# quark_dog_control.net
KiCad netlist of a schematic drawn in Altium Designer
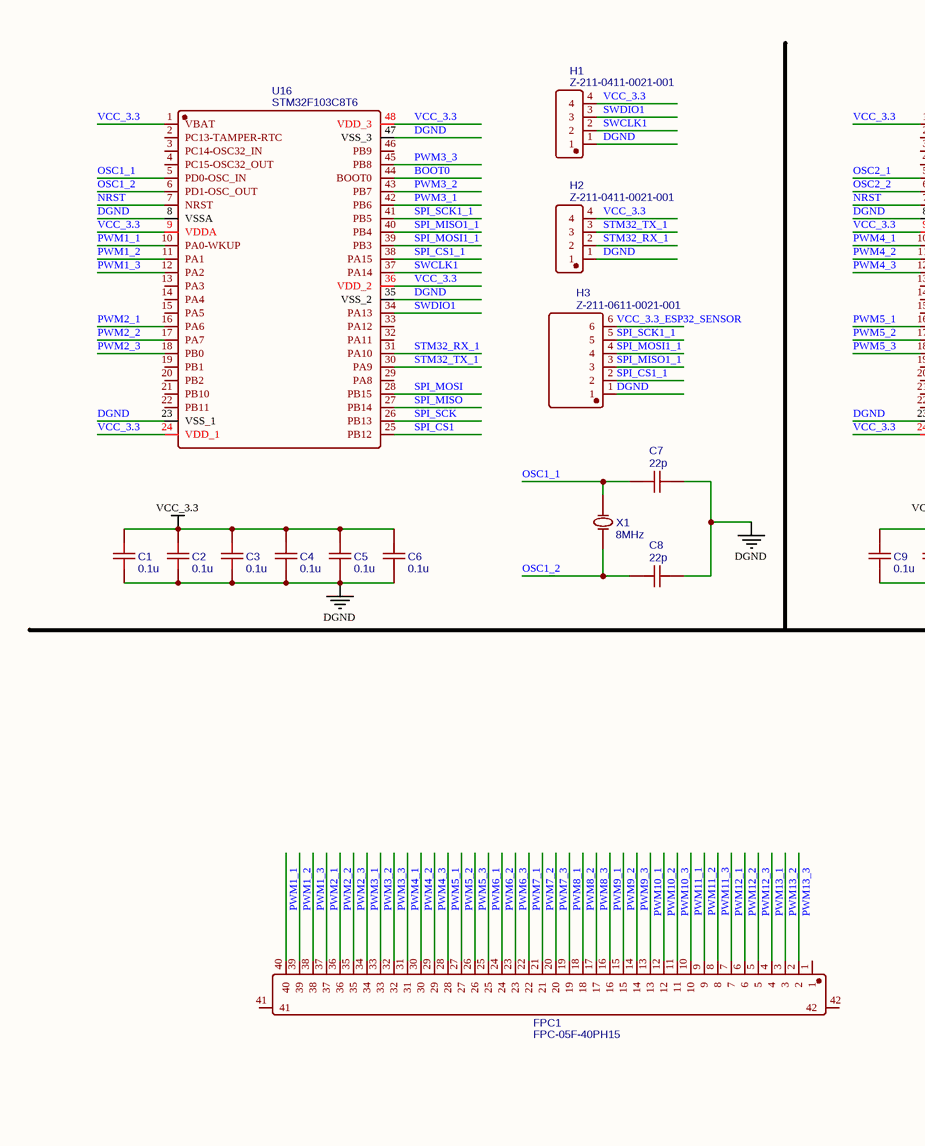
[diagram p0: quark_dog_control.schdoc, left]
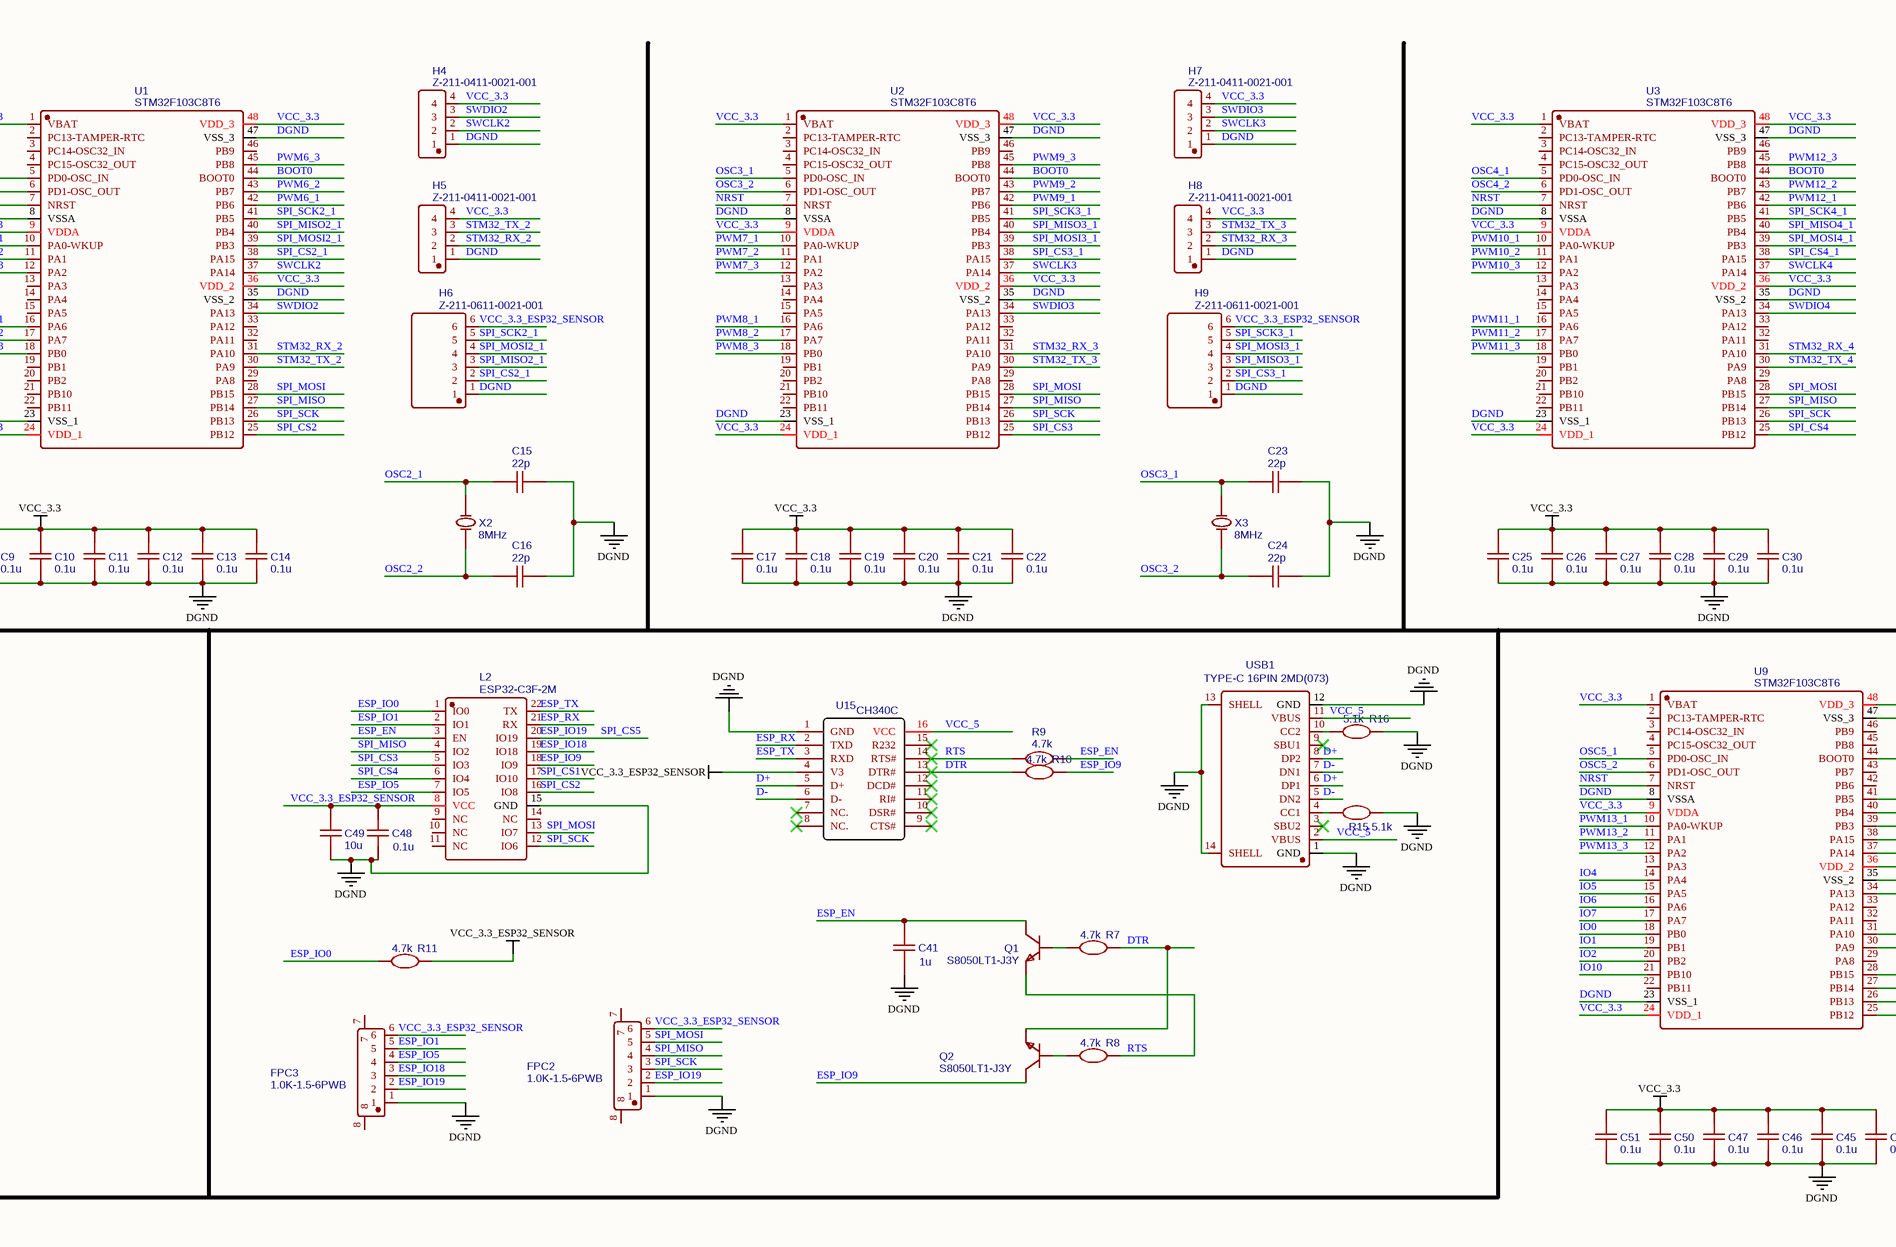
[diagram p1: quark_dog_control.schdoc, middle]
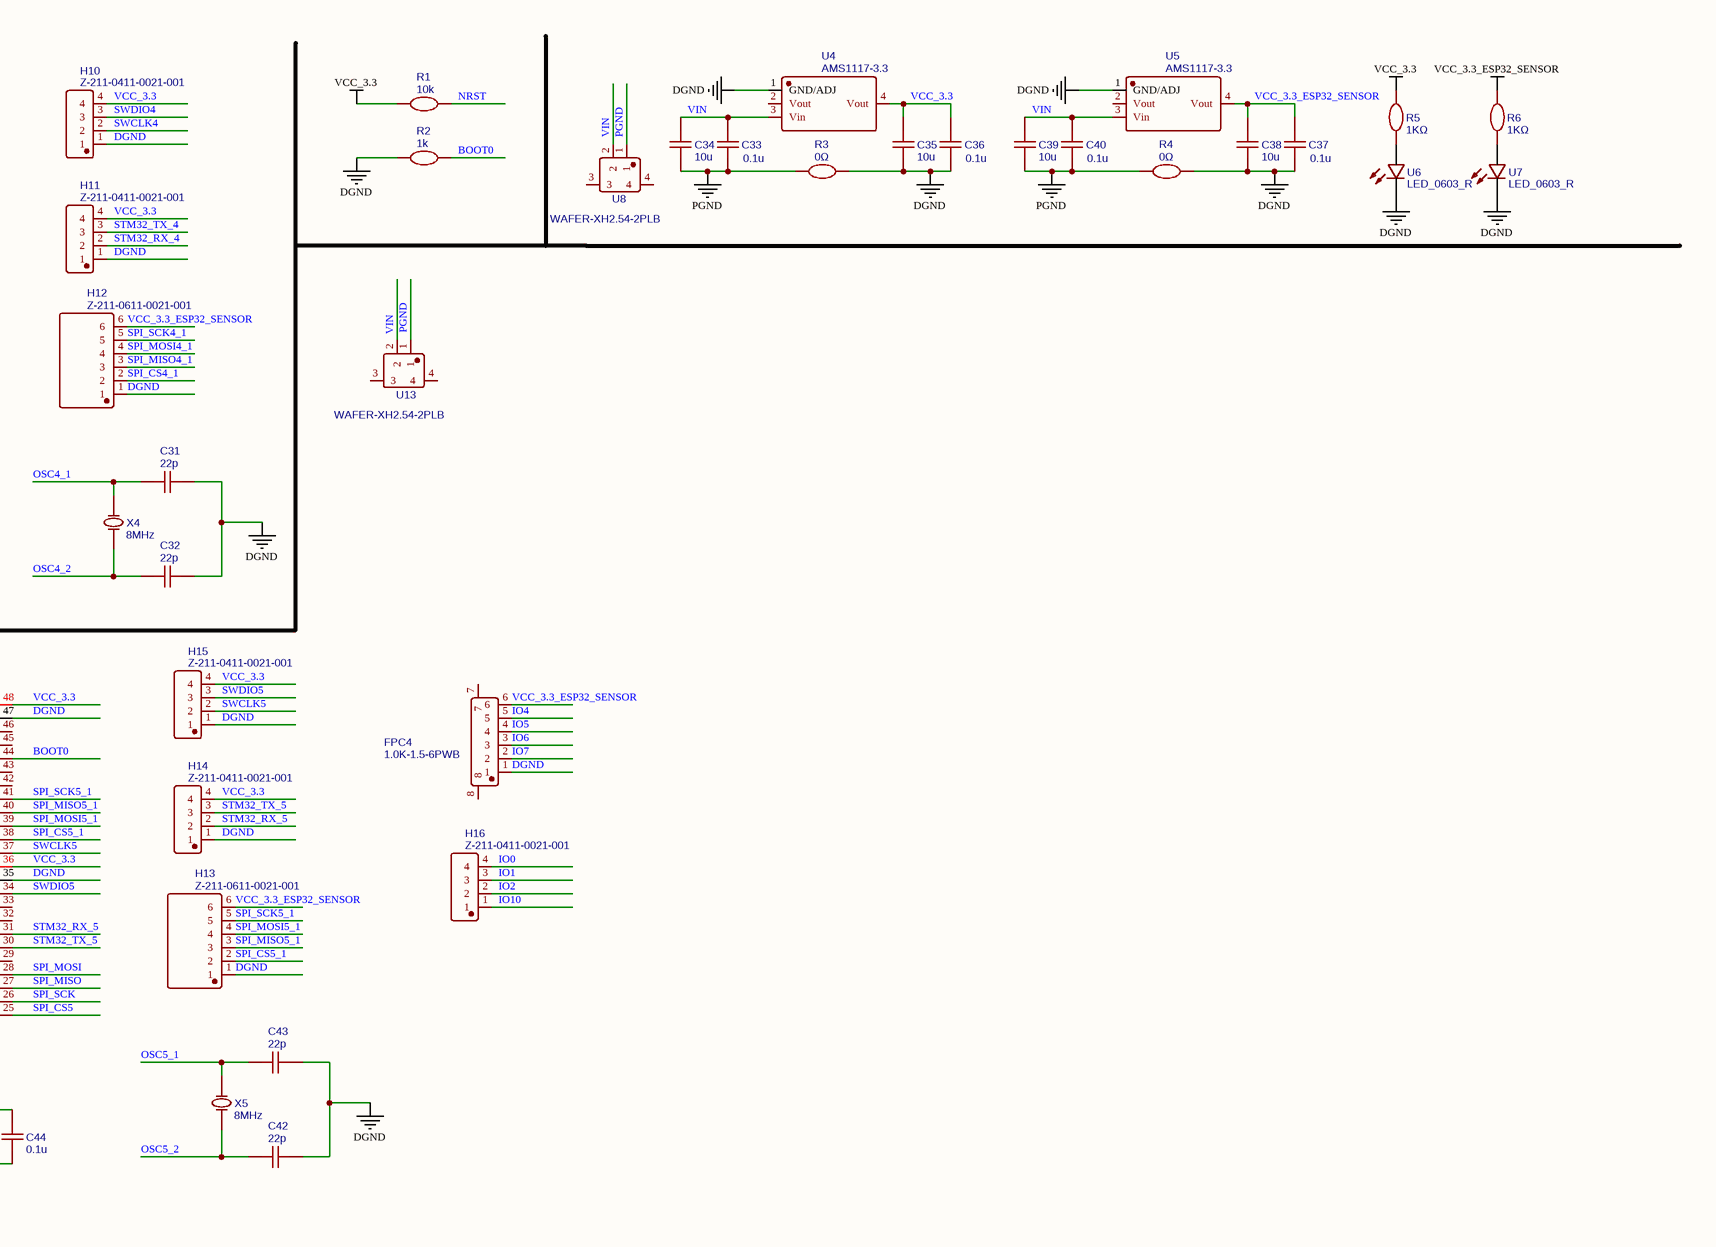
[diagram p2: quark_dog_control.schdoc, right]

(export (version "E")
  (design (tool "Eeschema 10.0.6"))
  (components
    (comp (ref "C1")
      (value "0.1u")
      (footprint "C0603")
      (fields (field (name "CONTRIBUTOR") "LCEDA_Lib"))
      (libsource (lib "altium-import") (part "root_1_0.1u_"))
    )
    (comp (ref "C2")
      (value "0.1u")
      (footprint "C0603")
      (fields (field (name "CONTRIBUTOR") "LCEDA_Lib"))
      (libsource (lib "altium-import") (part "root_1_0.1u_"))
    )
    (comp (ref "C3")
      (value "0.1u")
      (footprint "C0603")
      (fields (field (name "CONTRIBUTOR") "LCEDA_Lib"))
      (libsource (lib "altium-import") (part "root_1_0.1u_"))
    )
    (comp (ref "C4")
      (value "0.1u")
      (footprint "C0603")
      (fields (field (name "CONTRIBUTOR") "LCEDA_Lib"))
      (libsource (lib "altium-import") (part "root_1_0.1u_"))
    )
    (comp (ref "C5")
      (value "0.1u")
      (footprint "C0603")
      (fields (field (name "CONTRIBUTOR") "LCEDA_Lib"))
      (libsource (lib "altium-import") (part "root_1_0.1u_"))
    )
    (comp (ref "C6")
      (value "0.1u")
      (footprint "C0603")
      (fields (field (name "CONTRIBUTOR") "LCEDA_Lib"))
      (libsource (lib "altium-import") (part "root_1_0.1u_"))
    )
    (comp (ref "C7")
      (value "22p")
      (footprint "C0603")
      (fields (field (name "CONTRIBUTOR") "LCEDA_Lib"))
      (libsource (lib "altium-import") (part "root_2_22p_"))
    )
    (comp (ref "C8")
      (value "22p")
      (footprint "C0603")
      (fields (field (name "CONTRIBUTOR") "LCEDA_Lib"))
      (libsource (lib "altium-import") (part "root_0_22p_"))
    )
    (comp (ref "C9")
      (value "0.1u")
      (footprint "C0603")
      (fields (field (name "CONTRIBUTOR") "LCEDA_Lib"))
      (libsource (lib "altium-import") (part "root_1_0.1u_"))
    )
    (comp (ref "C10")
      (value "0.1u")
      (footprint "C0603")
      (fields (field (name "CONTRIBUTOR") "LCEDA_Lib"))
      (libsource (lib "altium-import") (part "root_1_0.1u_"))
    )
    (comp (ref "C11")
      (value "0.1u")
      (footprint "C0603")
      (fields (field (name "CONTRIBUTOR") "LCEDA_Lib"))
      (libsource (lib "altium-import") (part "root_1_0.1u_"))
    )
    (comp (ref "C12")
      (value "0.1u")
      (footprint "C0603")
      (fields (field (name "CONTRIBUTOR") "LCEDA_Lib"))
      (libsource (lib "altium-import") (part "root_1_0.1u_"))
    )
    (comp (ref "C13")
      (value "0.1u")
      (footprint "C0603")
      (fields (field (name "CONTRIBUTOR") "LCEDA_Lib"))
      (libsource (lib "altium-import") (part "root_1_0.1u_"))
    )
    (comp (ref "C14")
      (value "0.1u")
      (footprint "C0603")
      (fields (field (name "CONTRIBUTOR") "LCEDA_Lib"))
      (libsource (lib "altium-import") (part "root_1_0.1u_"))
    )
    (comp (ref "C15")
      (value "22p")
      (footprint "C0603")
      (fields (field (name "CONTRIBUTOR") "LCEDA_Lib"))
      (libsource (lib "altium-import") (part "root_2_22p_"))
    )
    (comp (ref "C16")
      (value "22p")
      (footprint "C0603")
      (fields (field (name "CONTRIBUTOR") "LCEDA_Lib"))
      (libsource (lib "altium-import") (part "root_0_22p_"))
    )
    (comp (ref "C17")
      (value "0.1u")
      (footprint "C0603")
      (fields (field (name "CONTRIBUTOR") "LCEDA_Lib"))
      (libsource (lib "altium-import") (part "root_1_0.1u_"))
    )
    (comp (ref "C18")
      (value "0.1u")
      (footprint "C0603")
      (fields (field (name "CONTRIBUTOR") "LCEDA_Lib"))
      (libsource (lib "altium-import") (part "root_1_0.1u_"))
    )
    (comp (ref "C19")
      (value "0.1u")
      (footprint "C0603")
      (fields (field (name "CONTRIBUTOR") "LCEDA_Lib"))
      (libsource (lib "altium-import") (part "root_1_0.1u_"))
    )
    (comp (ref "C20")
      (value "0.1u")
      (footprint "C0603")
      (fields (field (name "CONTRIBUTOR") "LCEDA_Lib"))
      (libsource (lib "altium-import") (part "root_1_0.1u_"))
    )
    (comp (ref "C21")
      (value "0.1u")
      (footprint "C0603")
      (fields (field (name "CONTRIBUTOR") "LCEDA_Lib"))
      (libsource (lib "altium-import") (part "root_1_0.1u_"))
    )
    (comp (ref "C22")
      (value "0.1u")
      (footprint "C0603")
      (fields (field (name "CONTRIBUTOR") "LCEDA_Lib"))
      (libsource (lib "altium-import") (part "root_1_0.1u_"))
    )
    (comp (ref "C23")
      (value "22p")
      (footprint "C0603")
      (fields (field (name "CONTRIBUTOR") "LCEDA_Lib"))
      (libsource (lib "altium-import") (part "root_2_22p_"))
    )
    (comp (ref "C24")
      (value "22p")
      (footprint "C0603")
      (fields (field (name "CONTRIBUTOR") "LCEDA_Lib"))
      (libsource (lib "altium-import") (part "root_0_22p_"))
    )
    (comp (ref "C25")
      (value "0.1u")
      (footprint "C0603")
      (fields (field (name "CONTRIBUTOR") "LCEDA_Lib"))
      (libsource (lib "altium-import") (part "root_1_0.1u_"))
    )
    (comp (ref "C26")
      (value "0.1u")
      (footprint "C0603")
      (fields (field (name "CONTRIBUTOR") "LCEDA_Lib"))
      (libsource (lib "altium-import") (part "root_1_0.1u_"))
    )
    (comp (ref "C27")
      (value "0.1u")
      (footprint "C0603")
      (fields (field (name "CONTRIBUTOR") "LCEDA_Lib"))
      (libsource (lib "altium-import") (part "root_1_0.1u_"))
    )
    (comp (ref "C28")
      (value "0.1u")
      (footprint "C0603")
      (fields (field (name "CONTRIBUTOR") "LCEDA_Lib"))
      (libsource (lib "altium-import") (part "root_1_0.1u_"))
    )
    (comp (ref "C29")
      (value "0.1u")
      (footprint "C0603")
      (fields (field (name "CONTRIBUTOR") "LCEDA_Lib"))
      (libsource (lib "altium-import") (part "root_1_0.1u_"))
    )
    (comp (ref "C30")
      (value "0.1u")
      (footprint "C0603")
      (fields (field (name "CONTRIBUTOR") "LCEDA_Lib"))
      (libsource (lib "altium-import") (part "root_1_0.1u_"))
    )
    (comp (ref "C31")
      (value "22p")
      (footprint "C0603")
      (fields (field (name "CONTRIBUTOR") "LCEDA_Lib"))
      (libsource (lib "altium-import") (part "root_2_22p_"))
    )
    (comp (ref "C32")
      (value "22p")
      (footprint "C0603")
      (fields (field (name "CONTRIBUTOR") "LCEDA_Lib"))
      (libsource (lib "altium-import") (part "root_0_22p_"))
    )
    (comp (ref "C33")
      (value "0.1u")
      (footprint "C0603")
      (fields (field (name "CONTRIBUTOR") "LCEDA_Lib"))
      (libsource (lib "altium-import") (part "root_1_0.1u_"))
    )
    (comp (ref "C34")
      (value "10u")
      (footprint "C0603")
      (fields (field (name "CONTRIBUTOR") "LCEDA_Lib"))
      (libsource (lib "altium-import") (part "root_1_10u_"))
    )
    (comp (ref "C35")
      (value "10u")
      (footprint "C0603")
      (fields (field (name "CONTRIBUTOR") "LCEDA_Lib"))
      (libsource (lib "altium-import") (part "root_1_10u_"))
    )
    (comp (ref "C36")
      (value "0.1u")
      (footprint "C0603")
      (fields (field (name "CONTRIBUTOR") "LCEDA_Lib"))
      (libsource (lib "altium-import") (part "root_1_0.1u_"))
    )
    (comp (ref "C37")
      (value "0.1u")
      (footprint "C0603")
      (fields (field (name "CONTRIBUTOR") "LCEDA_Lib"))
      (libsource (lib "altium-import") (part "root_1_0.1u_"))
    )
    (comp (ref "C38")
      (value "10u")
      (footprint "C0603")
      (fields (field (name "CONTRIBUTOR") "LCEDA_Lib"))
      (libsource (lib "altium-import") (part "root_1_10u_"))
    )
    (comp (ref "C39")
      (value "10u")
      (footprint "C0603")
      (fields (field (name "CONTRIBUTOR") "LCEDA_Lib"))
      (libsource (lib "altium-import") (part "root_1_10u_"))
    )
    (comp (ref "C40")
      (value "0.1u")
      (footprint "C0603")
      (fields (field (name "CONTRIBUTOR") "LCEDA_Lib"))
      (libsource (lib "altium-import") (part "root_1_0.1u_"))
    )
    (comp (ref "C41")
      (value "1u")
      (footprint "C0603")
      (fields (field (name "CONTRIBUTOR") "LCEDA_Lib"))
      (libsource (lib "altium-import") (part "root_1_1u_"))
    )
    (comp (ref "C42")
      (value "22p")
      (footprint "C0603")
      (fields (field (name "CONTRIBUTOR") "LCEDA_Lib"))
      (libsource (lib "altium-import") (part "root_0_22p_"))
    )
    (comp (ref "C43")
      (value "22p")
      (footprint "C0603")
      (fields (field (name "CONTRIBUTOR") "LCEDA_Lib"))
      (libsource (lib "altium-import") (part "root_2_22p_"))
    )
    (comp (ref "C44")
      (value "0.1u")
      (footprint "C0603")
      (fields (field (name "CONTRIBUTOR") "LCEDA_Lib"))
      (libsource (lib "altium-import") (part "root_1_0.1u_"))
    )
    (comp (ref "C45")
      (value "0.1u")
      (footprint "C0603")
      (fields (field (name "CONTRIBUTOR") "LCEDA_Lib"))
      (libsource (lib "altium-import") (part "root_1_0.1u_"))
    )
    (comp (ref "C46")
      (value "0.1u")
      (footprint "C0603")
      (fields (field (name "CONTRIBUTOR") "LCEDA_Lib"))
      (libsource (lib "altium-import") (part "root_1_0.1u_"))
    )
    (comp (ref "C47")
      (value "0.1u")
      (footprint "C0603")
      (fields (field (name "CONTRIBUTOR") "LCEDA_Lib"))
      (libsource (lib "altium-import") (part "root_1_0.1u_"))
    )
    (comp (ref "C48")
      (value "0.1u")
      (footprint "C0603")
      (fields (field (name "CONTRIBUTOR") "LCEDA_Lib"))
      (libsource (lib "altium-import") (part "root_1_0.1u_"))
    )
    (comp (ref "C49")
      (value "10u")
      (footprint "C0603")
      (fields (field (name "CONTRIBUTOR") "LCEDA_Lib"))
      (libsource (lib "altium-import") (part "root_1_10u_"))
    )
    (comp (ref "C50")
      (value "0.1u")
      (footprint "C0603")
      (fields (field (name "CONTRIBUTOR") "LCEDA_Lib"))
      (libsource (lib "altium-import") (part "root_1_0.1u_"))
    )
    (comp (ref "C51")
      (value "0.1u")
      (footprint "C0603")
      (fields (field (name "CONTRIBUTOR") "LCEDA_Lib"))
      (libsource (lib "altium-import") (part "root_1_0.1u_"))
    )
    (comp (ref "FPC1")
      (value "FPC-05F-40PH15")
      (footprint "FPC-SMD_40P-P0.50_FPC-05F-40PH15")
      (fields (field (name "BOM_SUPPLIER PART") "C2856825") (field (name "CONTRIBUTOR") "LCSC"))
      (libsource (lib "altium-import") (part "root_3_FPC-05F-40PH15_"))
    )
    (comp (ref "FPC2")
      (value "1.0K-1.5-6PWB")
      (footprint "FPC-SMD_6P-P1.00_HDGC_1.0K-1.5-6PWB")
      (fields (field (name "BOM_SUPPLIER PART") "C2919568") (field (name "CONTRIBUTOR") "LCSC"))
      (libsource (lib "altium-import") (part "root_2_1.0K-1.5-6PWB_"))
    )
    (comp (ref "FPC3")
      (value "1.0K-1.5-6PWB")
      (footprint "FPC-SMD_6P-P1.00_HDGC_1.0K-1.5-6PWB")
      (fields (field (name "BOM_SUPPLIER PART") "C2919568") (field (name "CONTRIBUTOR") "LCSC"))
      (libsource (lib "altium-import") (part "root_2_1.0K-1.5-6PWB_"))
    )
    (comp (ref "FPC4")
      (value "1.0K-1.5-6PWB")
      (footprint "FPC-SMD_6P-P1.00_HDGC_1.0K-1.5-6PWB")
      (fields (field (name "BOM_SUPPLIER PART") "C2919568") (field (name "CONTRIBUTOR") "LCSC"))
      (libsource (lib "altium-import") (part "root_2_1.0K-1.5-6PWB_"))
    )
    (comp (ref "H1")
      (value "Z-211-0411-0021-001")
      (footprint "HDR-TH_4P-P2.54-V-M")
      (fields (field (name "BOM_SUPPLIER PART") "C152150") (field (name "CONTRIBUTOR") "LCSC"))
      (libsource (lib "altium-import") (part "root_2_Z-211-0411-0021-001_"))
    )
    (comp (ref "H2")
      (value "Z-211-0411-0021-001")
      (footprint "HDR-TH_4P-P2.54-V-M")
      (fields (field (name "BOM_SUPPLIER PART") "C152150") (field (name "CONTRIBUTOR") "LCSC"))
      (libsource (lib "altium-import") (part "root_2_Z-211-0411-0021-001_"))
    )
    (comp (ref "H3")
      (value "Z-211-0611-0021-001")
      (footprint "HDR-TH_6P-P2.54-V_Z-211-0611-0021-001")
      (fields (field (name "BOM_SUPPLIER PART") "C190819") (field (name "CONTRIBUTOR") "LCSC"))
      (libsource (lib "altium-import") (part "root_2_Z-211-0611-0021-001_"))
    )
    (comp (ref "H4")
      (value "Z-211-0411-0021-001")
      (footprint "HDR-TH_4P-P2.54-V-M")
      (fields (field (name "BOM_SUPPLIER PART") "C152150") (field (name "CONTRIBUTOR") "LCSC"))
      (libsource (lib "altium-import") (part "root_2_Z-211-0411-0021-001_"))
    )
    (comp (ref "H5")
      (value "Z-211-0411-0021-001")
      (footprint "HDR-TH_4P-P2.54-V-M")
      (fields (field (name "BOM_SUPPLIER PART") "C152150") (field (name "CONTRIBUTOR") "LCSC"))
      (libsource (lib "altium-import") (part "root_2_Z-211-0411-0021-001_"))
    )
    (comp (ref "H6")
      (value "Z-211-0611-0021-001")
      (footprint "HDR-TH_6P-P2.54-V_Z-211-0611-0021-001")
      (fields (field (name "BOM_SUPPLIER PART") "C190819") (field (name "CONTRIBUTOR") "LCSC"))
      (libsource (lib "altium-import") (part "root_2_Z-211-0611-0021-001_"))
    )
    (comp (ref "H7")
      (value "Z-211-0411-0021-001")
      (footprint "HDR-TH_4P-P2.54-V-M")
      (fields (field (name "BOM_SUPPLIER PART") "C152150") (field (name "CONTRIBUTOR") "LCSC"))
      (libsource (lib "altium-import") (part "root_2_Z-211-0411-0021-001_"))
    )
    (comp (ref "H8")
      (value "Z-211-0411-0021-001")
      (footprint "HDR-TH_4P-P2.54-V-M")
      (fields (field (name "BOM_SUPPLIER PART") "C152150") (field (name "CONTRIBUTOR") "LCSC"))
      (libsource (lib "altium-import") (part "root_2_Z-211-0411-0021-001_"))
    )
    (comp (ref "H9")
      (value "Z-211-0611-0021-001")
      (footprint "HDR-TH_6P-P2.54-V_Z-211-0611-0021-001")
      (fields (field (name "BOM_SUPPLIER PART") "C190819") (field (name "CONTRIBUTOR") "LCSC"))
      (libsource (lib "altium-import") (part "root_2_Z-211-0611-0021-001_"))
    )
    (comp (ref "H10")
      (value "Z-211-0411-0021-001")
      (footprint "HDR-TH_4P-P2.54-V-M")
      (fields (field (name "BOM_SUPPLIER PART") "C152150") (field (name "CONTRIBUTOR") "LCSC"))
      (libsource (lib "altium-import") (part "root_2_Z-211-0411-0021-001_"))
    )
    (comp (ref "H11")
      (value "Z-211-0411-0021-001")
      (footprint "HDR-TH_4P-P2.54-V-M")
      (fields (field (name "BOM_SUPPLIER PART") "C152150") (field (name "CONTRIBUTOR") "LCSC"))
      (libsource (lib "altium-import") (part "root_2_Z-211-0411-0021-001_"))
    )
    (comp (ref "H12")
      (value "Z-211-0611-0021-001")
      (footprint "HDR-TH_6P-P2.54-V_Z-211-0611-0021-001")
      (fields (field (name "BOM_SUPPLIER PART") "C190819") (field (name "CONTRIBUTOR") "LCSC"))
      (libsource (lib "altium-import") (part "root_2_Z-211-0611-0021-001_"))
    )
    (comp (ref "H13")
      (value "Z-211-0611-0021-001")
      (footprint "HDR-TH_6P-P2.54-V_Z-211-0611-0021-001")
      (fields (field (name "BOM_SUPPLIER PART") "C190819") (field (name "CONTRIBUTOR") "LCSC"))
      (libsource (lib "altium-import") (part "root_2_Z-211-0611-0021-001_"))
    )
    (comp (ref "H14")
      (value "Z-211-0411-0021-001")
      (footprint "HDR-TH_4P-P2.54-V-M")
      (fields (field (name "BOM_SUPPLIER PART") "C152150") (field (name "CONTRIBUTOR") "LCSC"))
      (libsource (lib "altium-import") (part "root_2_Z-211-0411-0021-001_"))
    )
    (comp (ref "H15")
      (value "Z-211-0411-0021-001")
      (footprint "HDR-TH_4P-P2.54-V-M")
      (fields (field (name "BOM_SUPPLIER PART") "C152150") (field (name "CONTRIBUTOR") "LCSC"))
      (libsource (lib "altium-import") (part "root_2_Z-211-0411-0021-001_"))
    )
    (comp (ref "H16")
      (value "Z-211-0411-0021-001")
      (footprint "HDR-TH_4P-P2.54-V-M")
      (fields (field (name "BOM_SUPPLIER PART") "C152150") (field (name "CONTRIBUTOR") "LCSC"))
      (libsource (lib "altium-import") (part "root_2_Z-211-0411-0021-001_"))
    )
    (comp (ref "L2")
      (value "ESP32-C3F-2M")
      (footprint "WIFIM-SMD_ESP32-C3F-2M")
      (fields (field (name "BOM_SUPPLIER PART") "C2830867") (field (name "CONTRIBUTOR") "LCSC"))
      (libsource (lib "altium-import") (part "root_0_ESP32-C3F-2M_"))
    )
    (comp (ref "Q1")
      (value "S8050LT1-J3Y")
      (footprint "SOT-23_L2.9-W1.3-P1.90-LS2.4-BR")
      (fields (field (name "BOM_SUPPLIER PART") "C2962087") (field (name "CONTRIBUTOR") "lcsc"))
      (libsource (lib "altium-import") (part "root_0_S8050LT1-J3Y_"))
    )
    (comp (ref "Q2")
      (value "S8050LT1-J3Y")
      (footprint "SOT-23_L2.9-W1.3-P1.90-LS2.4-BR")
      (fields (field (name "BOM_SUPPLIER PART") "C2962087") (field (name "CONTRIBUTOR") "lcsc"))
      (libsource (lib "altium-import") (part "root_2_S8050LT1-J3Y_"))
    )
    (comp (ref "R1")
      (value "10k")
      (footprint "R0603")
      (fields (field (name "CONTRIBUTOR") "LCEDA_Lib"))
      (libsource (lib "altium-import") (part "root_0_10k_"))
    )
    (comp (ref "R2")
      (value "1k")
      (footprint "R0603")
      (fields (field (name "CONTRIBUTOR") "LCEDA_Lib"))
      (libsource (lib "altium-import") (part "root_0_1k_"))
    )
    (comp (ref "R3")
      (value "0Ω")
      (footprint "R0603")
      (fields (field (name "CONTRIBUTOR") "LCEDA_Lib"))
      (libsource (lib "altium-import") (part "root_0_0Ω_"))
    )
    (comp (ref "R4")
      (value "0Ω")
      (footprint "R0603")
      (fields (field (name "CONTRIBUTOR") "LCEDA_Lib"))
      (libsource (lib "altium-import") (part "root_0_0Ω_"))
    )
    (comp (ref "R5")
      (value "1KΩ")
      (footprint "R0603")
      (fields (field (name "CONTRIBUTOR") "LCEDA_Lib"))
      (libsource (lib "altium-import") (part "root_1_1KΩ_"))
    )
    (comp (ref "R6")
      (value "1KΩ")
      (footprint "R0603")
      (fields (field (name "CONTRIBUTOR") "LCEDA_Lib"))
      (libsource (lib "altium-import") (part "root_3_1KΩ_"))
    )
    (comp (ref "R7")
      (value "4.7k")
      (footprint "R0603")
      (fields (field (name "CONTRIBUTOR") "LCEDA_Lib"))
      (libsource (lib "altium-import") (part "root_0_4.7k_"))
    )
    (comp (ref "R8")
      (value "4.7k")
      (footprint "R0603")
      (fields (field (name "CONTRIBUTOR") "LCEDA_Lib"))
      (libsource (lib "altium-import") (part "root_0_4.7k_"))
    )
    (comp (ref "R9")
      (value "4.7k")
      (footprint "R0603")
      (fields (field (name "CONTRIBUTOR") "LCEDA_Lib"))
      (libsource (lib "altium-import") (part "root_2_4.7k_"))
    )
    (comp (ref "R10")
      (value "4.7k")
      (footprint "R0603")
      (fields (field (name "CONTRIBUTOR") "LCEDA_Lib"))
      (libsource (lib "altium-import") (part "root_0_4.7k_"))
    )
    (comp (ref "R11")
      (value "4.7k")
      (footprint "R0603")
      (fields (field (name "CONTRIBUTOR") "LCEDA_Lib"))
      (libsource (lib "altium-import") (part "root_0_4.7k_"))
    )
    (comp (ref "R15")
      (value "5.1k")
      (footprint "R0603")
      (fields (field (name "CONTRIBUTOR") "LCEDA_Lib"))
      (libsource (lib "altium-import") (part "root_0_5.1k_"))
    )
    (comp (ref "R16")
      (value "5.1k")
      (footprint "R0603")
      (fields (field (name "CONTRIBUTOR") "LCEDA_Lib"))
      (libsource (lib "altium-import") (part "root_0_5.1k_"))
    )
    (comp (ref "U1")
      (value "STM32F103C8T6")
      (footprint "LQFP-48_L7.0-W7.0-P0.50-LS9.0-BL")
      (fields (field (name "BOM_SUPPLIER PART") "C8734"))
      (libsource (lib "altium-import") (part "root_0_STM32F103C8T6_"))
    )
    (comp (ref "U2")
      (value "STM32F103C8T6")
      (footprint "LQFP-48_L7.0-W7.0-P0.50-LS9.0-BL")
      (fields (field (name "BOM_SUPPLIER PART") "C8734"))
      (libsource (lib "altium-import") (part "root_0_STM32F103C8T6_"))
    )
    (comp (ref "U3")
      (value "STM32F103C8T6")
      (footprint "LQFP-48_L7.0-W7.0-P0.50-LS9.0-BL")
      (fields (field (name "BOM_SUPPLIER PART") "C8734"))
      (libsource (lib "altium-import") (part "root_0_STM32F103C8T6_"))
    )
    (comp (ref "U4")
      (value "AMS1117-3.3")
      (footprint "SOT-223-3_L6.5-W3.4-P2.30-LS7.0-BR")
      (fields (field (name "BOM_SUPPLIER PART") "C6186"))
      (libsource (lib "altium-import") (part "root_0_AMS1117-3.3_"))
    )
    (comp (ref "U5")
      (value "AMS1117-3.3")
      (footprint "SOT-223-3_L6.5-W3.4-P2.30-LS7.0-BR")
      (fields (field (name "BOM_SUPPLIER PART") "C6186"))
      (libsource (lib "altium-import") (part "root_0_AMS1117-3.3_"))
    )
    (comp (ref "U6")
      (value "LED_0603_R")
      (footprint "LED0603-RD")
      (fields (field (name "BOM_SUPPLIER PART") "C9900016084") (field (name "CONTRIBUTOR") "lcsc"))
      (libsource (lib "altium-import") (part "root_1_LED_0603_R_"))
    )
    (comp (ref "U7")
      (value "LED_0603_R")
      (footprint "LED0603-RD")
      (fields (field (name "BOM_SUPPLIER PART") "C9900016084") (field (name "CONTRIBUTOR") "lcsc"))
      (libsource (lib "altium-import") (part "root_1_LED_0603_R_"))
    )
    (comp (ref "U8")
      (value "WAFER-XH2.54-2PLB")
      (footprint "CONN-SMD_2P-P2.50_XUNPU_WAFER-XH2.54-2PLB")
      (fields (field (name "BOM_SUPPLIER PART") "C3029467") (field (name "CONTRIBUTOR") "lcsc"))
      (libsource (lib "altium-import") (part "root_3_WAFER-XH2.54-2PLB_"))
    )
    (comp (ref "U9")
      (value "STM32F103C8T6")
      (footprint "LQFP-48_L7.0-W7.0-P0.50-LS9.0-BL")
      (fields (field (name "BOM_SUPPLIER PART") "C8734"))
      (libsource (lib "altium-import") (part "root_0_STM32F103C8T6_"))
    )
    (comp (ref "U13")
      (value "WAFER-XH2.54-2PLB")
      (footprint "CONN-SMD_2P-P2.50_XUNPU_WAFER-XH2.54-2PLB")
      (fields (field (name "BOM_SUPPLIER PART") "C3029467") (field (name "CONTRIBUTOR") "lcsc"))
      (libsource (lib "altium-import") (part "root_3_WAFER-XH2.54-2PLB_"))
    )
    (comp (ref "U15")
      (value "CH340C")
      (footprint "SOP-16_L10.0-W3.9-P1.27-LS6.0-BL")
      (fields (field (name "BOM_SUPPLIER PART") "C84681"))
      (libsource (lib "altium-import") (part "root_0_CH340C_"))
    )
    (comp (ref "U16")
      (value "STM32F103C8T6")
      (footprint "LQFP-48_L7.0-W7.0-P0.50-LS9.0-BL")
      (fields (field (name "BOM_SUPPLIER PART") "C8734"))
      (libsource (lib "altium-import") (part "root_0_STM32F103C8T6_"))
    )
    (comp (ref "USB1")
      (value "TYPE-C 16PIN 2MD(073)")
      (footprint "USB-C-SMD_TYPE-C-6PIN-2MD-073")
      (fields (field (name "BOM_SUPPLIER PART") "C2765186") (field (name "CONTRIBUTOR") "LCSC"))
      (libsource (lib "altium-import") (part "root_2_TYPE-C 16PIN 2MD(073)_"))
    )
    (comp (ref "X1")
      (value "8MHz")
      (footprint "OSC-SMD_L5.0-W3.2")
      (fields
        (field (name "BOM_SUPPLIER PART") "C331616")
        (field (name "BOM_MANUFACTURER PART") "7A08000001")
        (field (name "CONTRIBUTOR") "LCSC")
      )
      (libsource (lib "altium-import") (part "root_1_8MHz_"))
    )
    (comp (ref "X2")
      (value "8MHz")
      (footprint "OSC-SMD_L5.0-W3.2")
      (fields
        (field (name "BOM_SUPPLIER PART") "C331616")
        (field (name "BOM_MANUFACTURER PART") "7A08000001")
        (field (name "CONTRIBUTOR") "LCSC")
      )
      (libsource (lib "altium-import") (part "root_1_8MHz_"))
    )
    (comp (ref "X3")
      (value "8MHz")
      (footprint "OSC-SMD_L5.0-W3.2")
      (fields
        (field (name "BOM_SUPPLIER PART") "C331616")
        (field (name "BOM_MANUFACTURER PART") "7A08000001")
        (field (name "CONTRIBUTOR") "LCSC")
      )
      (libsource (lib "altium-import") (part "root_1_8MHz_"))
    )
    (comp (ref "X4")
      (value "8MHz")
      (footprint "OSC-SMD_L5.0-W3.2")
      (fields
        (field (name "BOM_SUPPLIER PART") "C331616")
        (field (name "BOM_MANUFACTURER PART") "7A08000001")
        (field (name "CONTRIBUTOR") "LCSC")
      )
      (libsource (lib "altium-import") (part "root_1_8MHz_"))
    )
    (comp (ref "X5")
      (value "8MHz")
      (footprint "OSC-SMD_L5.0-W3.2")
      (fields
        (field (name "BOM_SUPPLIER PART") "C331616")
        (field (name "BOM_MANUFACTURER PART") "7A08000001")
        (field (name "CONTRIBUTOR") "LCSC")
      )
      (libsource (lib "altium-import") (part "root_1_8MHz_"))
    )
  )
  (nets
    (net (code "1") (name "/BOOT0") (class "Default")
      (node (ref "R2") (pin "2") (pinfunction "2_2") (pintype "passive"))
      (node (ref "U1") (pin "44") (pinfunction "BOOT0_44") (pintype "passive"))
      (node (ref "U16") (pin "44") (pinfunction "BOOT0_44") (pintype "passive"))
      (node (ref "U2") (pin "44") (pinfunction "BOOT0_44") (pintype "passive"))
      (node (ref "U3") (pin "44") (pinfunction "BOOT0_44") (pintype "passive"))
      (node (ref "U9") (pin "44") (pinfunction "BOOT0_44") (pintype "passive"))
    )
    (net (code "2") (name "/D+") (class "Default")
      (node (ref "U15") (pin "5") (pinfunction "D+_5") (pintype "passive"))
      (node (ref "USB1") (pin "6") (pinfunction "DP1_6") (pintype "passive"))
      (node (ref "USB1") (pin "8") (pinfunction "DP2_8") (pintype "passive"))
    )
    (net (code "3") (name "/D-") (class "Default")
      (node (ref "U15") (pin "6") (pinfunction "D-_6") (pintype "passive"))
      (node (ref "USB1") (pin "5") (pinfunction "DN2_5") (pintype "passive"))
      (node (ref "USB1") (pin "7") (pinfunction "DN1_7") (pintype "passive"))
    )
    (net (code "4") (name "/DTR") (class "Default")
      (node (ref "Q2") (pin "2") (pinfunction "2_2") (pintype "passive"))
      (node (ref "R10") (pin "1") (pinfunction "1_1") (pintype "passive"))
      (node (ref "R7") (pin "2") (pinfunction "2_2") (pintype "passive"))
      (node (ref "U15") (pin "13") (pinfunction "DTR#_13") (pintype "passive"))
    )
    (net (code "5") (name "/ESP_EN") (class "Default")
      (node (ref "C41") (pin "2") (pinfunction "2_2") (pintype "passive"))
      (node (ref "L2") (pin "3") (pinfunction "EN_3") (pintype "passive"))
      (node (ref "Q1") (pin "3") (pinfunction "3_3") (pintype "passive"))
      (node (ref "R9") (pin "1") (pinfunction "1_1") (pintype "passive"))
    )
    (net (code "6") (name "/ESP_IO0") (class "Default")
      (node (ref "L2") (pin "1") (pinfunction "IO0_1") (pintype "passive"))
      (node (ref "R11") (pin "1") (pinfunction "1_1") (pintype "passive"))
    )
    (net (code "7") (name "/ESP_IO1") (class "Default")
      (node (ref "FPC3") (pin "5") (pinfunction "5_5") (pintype "passive"))
      (node (ref "L2") (pin "2") (pinfunction "IO1_2") (pintype "passive"))
    )
    (net (code "8") (name "/ESP_IO5") (class "Default")
      (node (ref "FPC3") (pin "4") (pinfunction "4_4") (pintype "passive"))
      (node (ref "L2") (pin "7") (pinfunction "IO5_7") (pintype "passive"))
    )
    (net (code "9") (name "/ESP_IO9") (class "Default")
      (node (ref "L2") (pin "18") (pinfunction "IO9_18") (pintype "passive"))
      (node (ref "Q2") (pin "3") (pinfunction "3_3") (pintype "passive"))
      (node (ref "R10") (pin "2") (pinfunction "2_2") (pintype "passive"))
    )
    (net (code "10") (name "/ESP_IO18") (class "Default")
      (node (ref "FPC3") (pin "3") (pinfunction "3_3") (pintype "passive"))
      (node (ref "L2") (pin "19") (pinfunction "IO18_19") (pintype "passive"))
    )
    (net (code "11") (name "/ESP_IO19") (class "Default")
      (node (ref "FPC2") (pin "2") (pinfunction "2_2") (pintype "passive"))
      (node (ref "FPC3") (pin "2") (pinfunction "2_2") (pintype "passive"))
      (node (ref "L2") (pin "20") (pinfunction "IO19_20") (pintype "passive"))
      (node (ref "U9") (pin "25") (pinfunction "PB12_25") (pintype "passive"))
    )
    (net (code "12") (name "/ESP_RX") (class "Default")
      (node (ref "L2") (pin "21") (pinfunction "RX_21") (pintype "passive"))
      (node (ref "U15") (pin "2") (pinfunction "TXD_2") (pintype "passive"))
    )
    (net (code "13") (name "/ESP_TX") (class "Default")
      (node (ref "L2") (pin "22") (pinfunction "TX_22") (pintype "passive"))
      (node (ref "U15") (pin "3") (pinfunction "RXD_3") (pintype "passive"))
    )
    (net (code "14") (name "/IO0") (class "Default")
      (node (ref "H16") (pin "4") (pinfunction "4_4") (pintype "passive"))
      (node (ref "U9") (pin "18") (pinfunction "PB0_18") (pintype "passive"))
    )
    (net (code "15") (name "/IO1") (class "Default")
      (node (ref "H16") (pin "3") (pinfunction "3_3") (pintype "passive"))
      (node (ref "U9") (pin "19") (pinfunction "PB1_19") (pintype "passive"))
    )
    (net (code "16") (name "/IO2") (class "Default")
      (node (ref "H16") (pin "2") (pinfunction "2_2") (pintype "passive"))
      (node (ref "U9") (pin "20") (pinfunction "PB2_20") (pintype "passive"))
    )
    (net (code "17") (name "/IO4") (class "Default")
      (node (ref "FPC4") (pin "5") (pinfunction "5_5") (pintype "passive"))
      (node (ref "U9") (pin "14") (pinfunction "PA4_14") (pintype "passive"))
    )
    (net (code "18") (name "/IO5") (class "Default")
      (node (ref "FPC4") (pin "4") (pinfunction "4_4") (pintype "passive"))
      (node (ref "U9") (pin "15") (pinfunction "PA5_15") (pintype "passive"))
    )
    (net (code "19") (name "/IO6") (class "Default")
      (node (ref "FPC4") (pin "3") (pinfunction "3_3") (pintype "passive"))
      (node (ref "U9") (pin "16") (pinfunction "PA6_16") (pintype "passive"))
    )
    (net (code "20") (name "/IO7") (class "Default")
      (node (ref "FPC4") (pin "2") (pinfunction "2_2") (pintype "passive"))
      (node (ref "U9") (pin "17") (pinfunction "PA7_17") (pintype "passive"))
    )
    (net (code "21") (name "/IO10") (class "Default")
      (node (ref "H16") (pin "1") (pinfunction "1_1") (pintype "passive"))
      (node (ref "U9") (pin "21") (pinfunction "PB10_21") (pintype "passive"))
    )
    (net (code "22") (name "/NRST") (class "Default")
      (node (ref "R1") (pin "2") (pinfunction "2_2") (pintype "passive"))
      (node (ref "U1") (pin "7") (pinfunction "NRST_7") (pintype "passive"))
      (node (ref "U16") (pin "7") (pinfunction "NRST_7") (pintype "passive"))
      (node (ref "U2") (pin "7") (pinfunction "NRST_7") (pintype "passive"))
      (node (ref "U3") (pin "7") (pinfunction "NRST_7") (pintype "passive"))
      (node (ref "U9") (pin "7") (pinfunction "NRST_7") (pintype "passive"))
    )
    (net (code "23") (name "/OSC1_1") (class "Default")
      (node (ref "C7") (pin "2") (pinfunction "2_2") (pintype "passive"))
      (node (ref "U16") (pin "5") (pinfunction "PD0-OSC_IN_5") (pintype "passive"))
      (node (ref "X1") (pin "2") (pinfunction "OSC2_2") (pintype "passive"))
    )
    (net (code "24") (name "/OSC1_2") (class "Default")
      (node (ref "C8") (pin "1") (pinfunction "1_1") (pintype "passive"))
      (node (ref "U16") (pin "6") (pinfunction "PD1-OSC_OUT_6") (pintype "passive"))
      (node (ref "X1") (pin "1") (pinfunction "OSC1_1") (pintype "passive"))
    )
    (net (code "25") (name "/OSC2_1") (class "Default")
      (node (ref "C15") (pin "2") (pinfunction "2_2") (pintype "passive"))
      (node (ref "U1") (pin "5") (pinfunction "PD0-OSC_IN_5") (pintype "passive"))
      (node (ref "X2") (pin "2") (pinfunction "OSC2_2") (pintype "passive"))
    )
    (net (code "26") (name "/OSC2_2") (class "Default")
      (node (ref "C16") (pin "1") (pinfunction "1_1") (pintype "passive"))
      (node (ref "U1") (pin "6") (pinfunction "PD1-OSC_OUT_6") (pintype "passive"))
      (node (ref "X2") (pin "1") (pinfunction "OSC1_1") (pintype "passive"))
    )
    (net (code "27") (name "/OSC3_1") (class "Default")
      (node (ref "C23") (pin "2") (pinfunction "2_2") (pintype "passive"))
      (node (ref "U2") (pin "5") (pinfunction "PD0-OSC_IN_5") (pintype "passive"))
      (node (ref "X3") (pin "2") (pinfunction "OSC2_2") (pintype "passive"))
    )
    (net (code "28") (name "/OSC3_2") (class "Default")
      (node (ref "C24") (pin "1") (pinfunction "1_1") (pintype "passive"))
      (node (ref "U2") (pin "6") (pinfunction "PD1-OSC_OUT_6") (pintype "passive"))
      (node (ref "X3") (pin "1") (pinfunction "OSC1_1") (pintype "passive"))
    )
    (net (code "29") (name "/OSC4_1") (class "Default")
      (node (ref "C31") (pin "2") (pinfunction "2_2") (pintype "passive"))
      (node (ref "U3") (pin "5") (pinfunction "PD0-OSC_IN_5") (pintype "passive"))
      (node (ref "X4") (pin "2") (pinfunction "OSC2_2") (pintype "passive"))
    )
    (net (code "30") (name "/OSC4_2") (class "Default")
      (node (ref "C32") (pin "1") (pinfunction "1_1") (pintype "passive"))
      (node (ref "U3") (pin "6") (pinfunction "PD1-OSC_OUT_6") (pintype "passive"))
      (node (ref "X4") (pin "1") (pinfunction "OSC1_1") (pintype "passive"))
    )
    (net (code "31") (name "/OSC5_1") (class "Default")
      (node (ref "C43") (pin "2") (pinfunction "2_2") (pintype "passive"))
      (node (ref "U9") (pin "5") (pinfunction "PD0-OSC_IN_5") (pintype "passive"))
      (node (ref "X5") (pin "2") (pinfunction "OSC2_2") (pintype "passive"))
    )
    (net (code "32") (name "/OSC5_2") (class "Default")
      (node (ref "C42") (pin "1") (pinfunction "1_1") (pintype "passive"))
      (node (ref "U9") (pin "6") (pinfunction "PD1-OSC_OUT_6") (pintype "passive"))
      (node (ref "X5") (pin "1") (pinfunction "OSC1_1") (pintype "passive"))
    )
    (net (code "33") (name "/PWM1_1") (class "Default")
      (node (ref "FPC1") (pin "40") (pinfunction "40_40") (pintype "passive"))
      (node (ref "U16") (pin "10") (pinfunction "PA0-WKUP_10") (pintype "passive"))
    )
    (net (code "34") (name "/PWM1_2") (class "Default")
      (node (ref "FPC1") (pin "39") (pinfunction "39_39") (pintype "passive"))
      (node (ref "U16") (pin "11") (pinfunction "PA1_11") (pintype "passive"))
    )
    (net (code "35") (name "/PWM1_3") (class "Default")
      (node (ref "FPC1") (pin "38") (pinfunction "38_38") (pintype "passive"))
      (node (ref "U16") (pin "12") (pinfunction "PA2_12") (pintype "passive"))
    )
    (net (code "36") (name "/PWM2_1") (class "Default")
      (node (ref "FPC1") (pin "37") (pinfunction "37_37") (pintype "passive"))
      (node (ref "U16") (pin "16") (pinfunction "PA6_16") (pintype "passive"))
    )
    (net (code "37") (name "/PWM2_2") (class "Default")
      (node (ref "FPC1") (pin "36") (pinfunction "36_36") (pintype "passive"))
      (node (ref "U16") (pin "17") (pinfunction "PA7_17") (pintype "passive"))
    )
    (net (code "38") (name "/PWM2_3") (class "Default")
      (node (ref "FPC1") (pin "35") (pinfunction "35_35") (pintype "passive"))
      (node (ref "U16") (pin "18") (pinfunction "PB0_18") (pintype "passive"))
    )
    (net (code "39") (name "/PWM3_1") (class "Default")
      (node (ref "FPC1") (pin "34") (pinfunction "34_34") (pintype "passive"))
      (node (ref "U16") (pin "42") (pinfunction "PB6_42") (pintype "passive"))
    )
    (net (code "40") (name "/PWM3_2") (class "Default")
      (node (ref "FPC1") (pin "33") (pinfunction "33_33") (pintype "passive"))
      (node (ref "U16") (pin "43") (pinfunction "PB7_43") (pintype "passive"))
    )
    (net (code "41") (name "/PWM3_3") (class "Default")
      (node (ref "FPC1") (pin "32") (pinfunction "32_32") (pintype "passive"))
      (node (ref "U16") (pin "45") (pinfunction "PB8_45") (pintype "passive"))
    )
    (net (code "42") (name "/PWM4_1") (class "Default")
      (node (ref "FPC1") (pin "31") (pinfunction "31_31") (pintype "passive"))
      (node (ref "U1") (pin "10") (pinfunction "PA0-WKUP_10") (pintype "passive"))
    )
    (net (code "43") (name "/PWM4_2") (class "Default")
      (node (ref "FPC1") (pin "30") (pinfunction "30_30") (pintype "passive"))
      (node (ref "U1") (pin "11") (pinfunction "PA1_11") (pintype "passive"))
    )
    (net (code "44") (name "/PWM4_3") (class "Default")
      (node (ref "FPC1") (pin "29") (pinfunction "29_29") (pintype "passive"))
      (node (ref "U1") (pin "12") (pinfunction "PA2_12") (pintype "passive"))
    )
    (net (code "45") (name "/PWM5_1") (class "Default")
      (node (ref "FPC1") (pin "28") (pinfunction "28_28") (pintype "passive"))
      (node (ref "U1") (pin "16") (pinfunction "PA6_16") (pintype "passive"))
    )
    (net (code "46") (name "/PWM5_2") (class "Default")
      (node (ref "FPC1") (pin "27") (pinfunction "27_27") (pintype "passive"))
      (node (ref "U1") (pin "17") (pinfunction "PA7_17") (pintype "passive"))
    )
    (net (code "47") (name "/PWM5_3") (class "Default")
      (node (ref "FPC1") (pin "26") (pinfunction "26_26") (pintype "passive"))
      (node (ref "U1") (pin "18") (pinfunction "PB0_18") (pintype "passive"))
    )
    (net (code "48") (name "/PWM6_1") (class "Default")
      (node (ref "FPC1") (pin "25") (pinfunction "25_25") (pintype "passive"))
      (node (ref "U1") (pin "42") (pinfunction "PB6_42") (pintype "passive"))
    )
    (net (code "49") (name "/PWM6_2") (class "Default")
      (node (ref "FPC1") (pin "24") (pinfunction "24_24") (pintype "passive"))
      (node (ref "U1") (pin "43") (pinfunction "PB7_43") (pintype "passive"))
    )
    (net (code "50") (name "/PWM6_3") (class "Default")
      (node (ref "FPC1") (pin "23") (pinfunction "23_23") (pintype "passive"))
      (node (ref "U1") (pin "45") (pinfunction "PB8_45") (pintype "passive"))
    )
    (net (code "51") (name "/PWM7_1") (class "Default")
      (node (ref "FPC1") (pin "22") (pinfunction "22_22") (pintype "passive"))
      (node (ref "U2") (pin "10") (pinfunction "PA0-WKUP_10") (pintype "passive"))
    )
    (net (code "52") (name "/PWM7_2") (class "Default")
      (node (ref "FPC1") (pin "21") (pinfunction "21_21") (pintype "passive"))
      (node (ref "U2") (pin "11") (pinfunction "PA1_11") (pintype "passive"))
    )
    (net (code "53") (name "/PWM7_3") (class "Default")
      (node (ref "FPC1") (pin "20") (pinfunction "20_20") (pintype "passive"))
      (node (ref "U2") (pin "12") (pinfunction "PA2_12") (pintype "passive"))
    )
    (net (code "54") (name "/PWM8_1") (class "Default")
      (node (ref "FPC1") (pin "19") (pinfunction "19_19") (pintype "passive"))
      (node (ref "U2") (pin "16") (pinfunction "PA6_16") (pintype "passive"))
    )
    (net (code "55") (name "/PWM8_2") (class "Default")
      (node (ref "FPC1") (pin "18") (pinfunction "18_18") (pintype "passive"))
      (node (ref "U2") (pin "17") (pinfunction "PA7_17") (pintype "passive"))
    )
    (net (code "56") (name "/PWM8_3") (class "Default")
      (node (ref "FPC1") (pin "17") (pinfunction "17_17") (pintype "passive"))
      (node (ref "U2") (pin "18") (pinfunction "PB0_18") (pintype "passive"))
    )
    (net (code "57") (name "/PWM9_1") (class "Default")
      (node (ref "FPC1") (pin "16") (pinfunction "16_16") (pintype "passive"))
      (node (ref "U2") (pin "42") (pinfunction "PB6_42") (pintype "passive"))
    )
    (net (code "58") (name "/PWM9_2") (class "Default")
      (node (ref "FPC1") (pin "15") (pinfunction "15_15") (pintype "passive"))
      (node (ref "U2") (pin "43") (pinfunction "PB7_43") (pintype "passive"))
    )
    (net (code "59") (name "/PWM9_3") (class "Default")
      (node (ref "FPC1") (pin "14") (pinfunction "14_14") (pintype "passive"))
      (node (ref "U2") (pin "45") (pinfunction "PB8_45") (pintype "passive"))
    )
    (net (code "60") (name "/PWM10_1") (class "Default")
      (node (ref "FPC1") (pin "13") (pinfunction "13_13") (pintype "passive"))
      (node (ref "U3") (pin "10") (pinfunction "PA0-WKUP_10") (pintype "passive"))
    )
    (net (code "61") (name "/PWM10_2") (class "Default")
      (node (ref "FPC1") (pin "12") (pinfunction "12_12") (pintype "passive"))
      (node (ref "U3") (pin "11") (pinfunction "PA1_11") (pintype "passive"))
    )
    (net (code "62") (name "/PWM10_3") (class "Default")
      (node (ref "FPC1") (pin "11") (pinfunction "11_11") (pintype "passive"))
      (node (ref "U3") (pin "12") (pinfunction "PA2_12") (pintype "passive"))
    )
    (net (code "63") (name "/PWM11_1") (class "Default")
      (node (ref "FPC1") (pin "10") (pinfunction "10_10") (pintype "passive"))
      (node (ref "U3") (pin "16") (pinfunction "PA6_16") (pintype "passive"))
    )
    (net (code "64") (name "/PWM11_2") (class "Default")
      (node (ref "FPC1") (pin "9") (pinfunction "9_9") (pintype "passive"))
      (node (ref "U3") (pin "17") (pinfunction "PA7_17") (pintype "passive"))
    )
    (net (code "65") (name "/PWM11_3") (class "Default")
      (node (ref "FPC1") (pin "8") (pinfunction "8_8") (pintype "passive"))
      (node (ref "U3") (pin "18") (pinfunction "PB0_18") (pintype "passive"))
    )
    (net (code "66") (name "/PWM12_1") (class "Default")
      (node (ref "FPC1") (pin "7") (pinfunction "7_7") (pintype "passive"))
      (node (ref "U3") (pin "42") (pinfunction "PB6_42") (pintype "passive"))
    )
    (net (code "67") (name "/PWM12_2") (class "Default")
      (node (ref "FPC1") (pin "6") (pinfunction "6_6") (pintype "passive"))
      (node (ref "U3") (pin "43") (pinfunction "PB7_43") (pintype "passive"))
    )
    (net (code "68") (name "/PWM12_3") (class "Default")
      (node (ref "FPC1") (pin "5") (pinfunction "5_5") (pintype "passive"))
      (node (ref "U3") (pin "45") (pinfunction "PB8_45") (pintype "passive"))
    )
    (net (code "69") (name "/PWM13_1") (class "Default")
      (node (ref "FPC1") (pin "4") (pinfunction "4_4") (pintype "passive"))
      (node (ref "U9") (pin "10") (pinfunction "PA0-WKUP_10") (pintype "passive"))
    )
    (net (code "70") (name "/PWM13_2") (class "Default")
      (node (ref "FPC1") (pin "3") (pinfunction "3_3") (pintype "passive"))
      (node (ref "U9") (pin "11") (pinfunction "PA1_11") (pintype "passive"))
    )
    (net (code "71") (name "/PWM13_3") (class "Default")
      (node (ref "FPC1") (pin "2") (pinfunction "2_2") (pintype "passive"))
      (node (ref "U9") (pin "12") (pinfunction "PA2_12") (pintype "passive"))
    )
    (net (code "72") (name "/RTS") (class "Default")
      (node (ref "Q1") (pin "2") (pinfunction "2_2") (pintype "passive"))
      (node (ref "R8") (pin "2") (pinfunction "2_2") (pintype "passive"))
      (node (ref "R9") (pin "2") (pinfunction "2_2") (pintype "passive"))
      (node (ref "U15") (pin "14") (pinfunction "RTS#_14") (pintype "passive"))
    )
    (net (code "73") (name "/SPI_CS1") (class "Default")
      (node (ref "L2") (pin "17") (pinfunction "IO10_17") (pintype "passive"))
      (node (ref "U16") (pin "25") (pinfunction "PB12_25") (pintype "passive"))
    )
    (net (code "74") (name "/SPI_CS1_1") (class "Default")
      (node (ref "H3") (pin "2") (pinfunction "2_2") (pintype "passive"))
      (node (ref "U16") (pin "38") (pinfunction "PA15_38") (pintype "passive"))
    )
    (net (code "75") (name "/SPI_CS2") (class "Default")
      (node (ref "L2") (pin "16") (pinfunction "IO8_16") (pintype "passive"))
      (node (ref "U1") (pin "25") (pinfunction "PB12_25") (pintype "passive"))
    )
    (net (code "76") (name "/SPI_CS2_1") (class "Default")
      (node (ref "H6") (pin "2") (pinfunction "2_2") (pintype "passive"))
      (node (ref "U1") (pin "38") (pinfunction "PA15_38") (pintype "passive"))
    )
    (net (code "77") (name "/SPI_CS3") (class "Default")
      (node (ref "L2") (pin "5") (pinfunction "IO3_5") (pintype "passive"))
      (node (ref "U2") (pin "25") (pinfunction "PB12_25") (pintype "passive"))
    )
    (net (code "78") (name "/SPI_CS3_1") (class "Default")
      (node (ref "H9") (pin "2") (pinfunction "2_2") (pintype "passive"))
      (node (ref "U2") (pin "38") (pinfunction "PA15_38") (pintype "passive"))
    )
    (net (code "79") (name "/SPI_CS4") (class "Default")
      (node (ref "L2") (pin "6") (pinfunction "IO4_6") (pintype "passive"))
      (node (ref "U3") (pin "25") (pinfunction "PB12_25") (pintype "passive"))
    )
    (net (code "80") (name "/SPI_CS4_1") (class "Default")
      (node (ref "H12") (pin "2") (pinfunction "2_2") (pintype "passive"))
      (node (ref "U3") (pin "38") (pinfunction "PA15_38") (pintype "passive"))
    )
    (net (code "81") (name "/SPI_CS5_1") (class "Default")
      (node (ref "H13") (pin "2") (pinfunction "2_2") (pintype "passive"))
      (node (ref "U9") (pin "38") (pinfunction "PA15_38") (pintype "passive"))
    )
    (net (code "82") (name "/SPI_MISO") (class "Default")
      (node (ref "FPC2") (pin "4") (pinfunction "4_4") (pintype "passive"))
      (node (ref "L2") (pin "4") (pinfunction "IO2_4") (pintype "passive"))
      (node (ref "U1") (pin "27") (pinfunction "PB14_27") (pintype "passive"))
      (node (ref "U16") (pin "27") (pinfunction "PB14_27") (pintype "passive"))
      (node (ref "U2") (pin "27") (pinfunction "PB14_27") (pintype "passive"))
      (node (ref "U3") (pin "27") (pinfunction "PB14_27") (pintype "passive"))
      (node (ref "U9") (pin "27") (pinfunction "PB14_27") (pintype "passive"))
    )
    (net (code "83") (name "/SPI_MISO1_1") (class "Default")
      (node (ref "H3") (pin "3") (pinfunction "3_3") (pintype "passive"))
      (node (ref "U16") (pin "40") (pinfunction "PB4_40") (pintype "passive"))
    )
    (net (code "84") (name "/SPI_MISO2_1") (class "Default")
      (node (ref "H6") (pin "3") (pinfunction "3_3") (pintype "passive"))
      (node (ref "U1") (pin "40") (pinfunction "PB4_40") (pintype "passive"))
    )
    (net (code "85") (name "/SPI_MISO3_1") (class "Default")
      (node (ref "H9") (pin "3") (pinfunction "3_3") (pintype "passive"))
      (node (ref "U2") (pin "40") (pinfunction "PB4_40") (pintype "passive"))
    )
    (net (code "86") (name "/SPI_MISO4_1") (class "Default")
      (node (ref "H12") (pin "3") (pinfunction "3_3") (pintype "passive"))
      (node (ref "U3") (pin "40") (pinfunction "PB4_40") (pintype "passive"))
    )
    (net (code "87") (name "/SPI_MISO5_1") (class "Default")
      (node (ref "H13") (pin "3") (pinfunction "3_3") (pintype "passive"))
      (node (ref "U9") (pin "40") (pinfunction "PB4_40") (pintype "passive"))
    )
    (net (code "88") (name "/SPI_MOSI") (class "Default")
      (node (ref "FPC2") (pin "5") (pinfunction "5_5") (pintype "passive"))
      (node (ref "L2") (pin "13") (pinfunction "IO7_13") (pintype "passive"))
      (node (ref "U1") (pin "28") (pinfunction "PB15_28") (pintype "passive"))
      (node (ref "U16") (pin "28") (pinfunction "PB15_28") (pintype "passive"))
      (node (ref "U2") (pin "28") (pinfunction "PB15_28") (pintype "passive"))
      (node (ref "U3") (pin "28") (pinfunction "PB15_28") (pintype "passive"))
      (node (ref "U9") (pin "28") (pinfunction "PB15_28") (pintype "passive"))
    )
    (net (code "89") (name "/SPI_MOSI1_1") (class "Default")
      (node (ref "H3") (pin "4") (pinfunction "4_4") (pintype "passive"))
      (node (ref "U16") (pin "39") (pinfunction "PB3_39") (pintype "passive"))
    )
    (net (code "90") (name "/SPI_MOSI2_1") (class "Default")
      (node (ref "H6") (pin "4") (pinfunction "4_4") (pintype "passive"))
      (node (ref "U1") (pin "39") (pinfunction "PB3_39") (pintype "passive"))
    )
    (net (code "91") (name "/SPI_MOSI3_1") (class "Default")
      (node (ref "H9") (pin "4") (pinfunction "4_4") (pintype "passive"))
      (node (ref "U2") (pin "39") (pinfunction "PB3_39") (pintype "passive"))
    )
    (net (code "92") (name "/SPI_MOSI4_1") (class "Default")
      (node (ref "H12") (pin "4") (pinfunction "4_4") (pintype "passive"))
      (node (ref "U3") (pin "39") (pinfunction "PB3_39") (pintype "passive"))
    )
    (net (code "93") (name "/SPI_MOSI5_1") (class "Default")
      (node (ref "H13") (pin "4") (pinfunction "4_4") (pintype "passive"))
      (node (ref "U9") (pin "39") (pinfunction "PB3_39") (pintype "passive"))
    )
    (net (code "94") (name "/SPI_SCK") (class "Default")
      (node (ref "FPC2") (pin "3") (pinfunction "3_3") (pintype "passive"))
      (node (ref "L2") (pin "12") (pinfunction "IO6_12") (pintype "passive"))
      (node (ref "U1") (pin "26") (pinfunction "PB13_26") (pintype "passive"))
      (node (ref "U16") (pin "26") (pinfunction "PB13_26") (pintype "passive"))
      (node (ref "U2") (pin "26") (pinfunction "PB13_26") (pintype "passive"))
      (node (ref "U3") (pin "26") (pinfunction "PB13_26") (pintype "passive"))
      (node (ref "U9") (pin "26") (pinfunction "PB13_26") (pintype "passive"))
    )
    (net (code "95") (name "/SPI_SCK1_1") (class "Default")
      (node (ref "H3") (pin "5") (pinfunction "5_5") (pintype "passive"))
      (node (ref "U16") (pin "41") (pinfunction "PB5_41") (pintype "passive"))
    )
    (net (code "96") (name "/SPI_SCK2_1") (class "Default")
      (node (ref "H6") (pin "5") (pinfunction "5_5") (pintype "passive"))
      (node (ref "U1") (pin "41") (pinfunction "PB5_41") (pintype "passive"))
    )
    (net (code "97") (name "/SPI_SCK3_1") (class "Default")
      (node (ref "H9") (pin "5") (pinfunction "5_5") (pintype "passive"))
      (node (ref "U2") (pin "41") (pinfunction "PB5_41") (pintype "passive"))
    )
    (net (code "98") (name "/SPI_SCK4_1") (class "Default")
      (node (ref "H12") (pin "5") (pinfunction "5_5") (pintype "passive"))
      (node (ref "U3") (pin "41") (pinfunction "PB5_41") (pintype "passive"))
    )
    (net (code "99") (name "/SPI_SCK5_1") (class "Default")
      (node (ref "H13") (pin "5") (pinfunction "5_5") (pintype "passive"))
      (node (ref "U9") (pin "41") (pinfunction "PB5_41") (pintype "passive"))
    )
    (net (code "100") (name "/STM32_RX_1") (class "Default")
      (node (ref "H2") (pin "2") (pinfunction "2_2") (pintype "passive"))
      (node (ref "U16") (pin "31") (pinfunction "PA10_31") (pintype "passive"))
    )
    (net (code "101") (name "/STM32_RX_2") (class "Default")
      (node (ref "H5") (pin "2") (pinfunction "2_2") (pintype "passive"))
      (node (ref "U1") (pin "31") (pinfunction "PA10_31") (pintype "passive"))
    )
    (net (code "102") (name "/STM32_RX_3") (class "Default")
      (node (ref "H8") (pin "2") (pinfunction "2_2") (pintype "passive"))
      (node (ref "U2") (pin "31") (pinfunction "PA10_31") (pintype "passive"))
    )
    (net (code "103") (name "/STM32_RX_4") (class "Default")
      (node (ref "H11") (pin "2") (pinfunction "2_2") (pintype "passive"))
      (node (ref "U3") (pin "31") (pinfunction "PA10_31") (pintype "passive"))
    )
    (net (code "104") (name "/STM32_RX_5") (class "Default")
      (node (ref "H14") (pin "2") (pinfunction "2_2") (pintype "passive"))
      (node (ref "U9") (pin "31") (pinfunction "PA10_31") (pintype "passive"))
    )
    (net (code "105") (name "/STM32_TX_1") (class "Default")
      (node (ref "H2") (pin "3") (pinfunction "3_3") (pintype "passive"))
      (node (ref "U16") (pin "30") (pinfunction "PA9_30") (pintype "passive"))
    )
    (net (code "106") (name "/STM32_TX_2") (class "Default")
      (node (ref "H5") (pin "3") (pinfunction "3_3") (pintype "passive"))
      (node (ref "U1") (pin "30") (pinfunction "PA9_30") (pintype "passive"))
    )
    (net (code "107") (name "/STM32_TX_3") (class "Default")
      (node (ref "H8") (pin "3") (pinfunction "3_3") (pintype "passive"))
      (node (ref "U2") (pin "30") (pinfunction "PA9_30") (pintype "passive"))
    )
    (net (code "108") (name "/STM32_TX_4") (class "Default")
      (node (ref "H11") (pin "3") (pinfunction "3_3") (pintype "passive"))
      (node (ref "U3") (pin "30") (pinfunction "PA9_30") (pintype "passive"))
    )
    (net (code "109") (name "/STM32_TX_5") (class "Default")
      (node (ref "H14") (pin "3") (pinfunction "3_3") (pintype "passive"))
      (node (ref "U9") (pin "30") (pinfunction "PA9_30") (pintype "passive"))
    )
    (net (code "110") (name "/SWCLK1") (class "Default")
      (node (ref "H1") (pin "2") (pinfunction "2_2") (pintype "passive"))
      (node (ref "U16") (pin "37") (pinfunction "PA14_37") (pintype "passive"))
    )
    (net (code "111") (name "/SWCLK2") (class "Default")
      (node (ref "H4") (pin "2") (pinfunction "2_2") (pintype "passive"))
      (node (ref "U1") (pin "37") (pinfunction "PA14_37") (pintype "passive"))
    )
    (net (code "112") (name "/SWCLK3") (class "Default")
      (node (ref "H7") (pin "2") (pinfunction "2_2") (pintype "passive"))
      (node (ref "U2") (pin "37") (pinfunction "PA14_37") (pintype "passive"))
    )
    (net (code "113") (name "/SWCLK4") (class "Default")
      (node (ref "H10") (pin "2") (pinfunction "2_2") (pintype "passive"))
      (node (ref "U3") (pin "37") (pinfunction "PA14_37") (pintype "passive"))
    )
    (net (code "114") (name "/SWCLK5") (class "Default")
      (node (ref "H15") (pin "2") (pinfunction "2_2") (pintype "passive"))
      (node (ref "U9") (pin "37") (pinfunction "PA14_37") (pintype "passive"))
    )
    (net (code "115") (name "/SWDIO1") (class "Default")
      (node (ref "H1") (pin "3") (pinfunction "3_3") (pintype "passive"))
      (node (ref "U16") (pin "34") (pinfunction "PA13_34") (pintype "passive"))
    )
    (net (code "116") (name "/SWDIO2") (class "Default")
      (node (ref "H4") (pin "3") (pinfunction "3_3") (pintype "passive"))
      (node (ref "U1") (pin "34") (pinfunction "PA13_34") (pintype "passive"))
    )
    (net (code "117") (name "/SWDIO3") (class "Default")
      (node (ref "H7") (pin "3") (pinfunction "3_3") (pintype "passive"))
      (node (ref "U2") (pin "34") (pinfunction "PA13_34") (pintype "passive"))
    )
    (net (code "118") (name "/SWDIO4") (class "Default")
      (node (ref "H10") (pin "3") (pinfunction "3_3") (pintype "passive"))
      (node (ref "U3") (pin "34") (pinfunction "PA13_34") (pintype "passive"))
    )
    (net (code "119") (name "/SWDIO5") (class "Default")
      (node (ref "H15") (pin "3") (pinfunction "3_3") (pintype "passive"))
      (node (ref "U9") (pin "34") (pinfunction "PA13_34") (pintype "passive"))
    )
    (net (code "120") (name "/VCC_5") (class "Default")
      (node (ref "U15") (pin "16") (pinfunction "VCC_16") (pintype "passive"))
      (node (ref "USB1") (pin "11") (pinfunction "VBUS_11") (pintype "passive"))
      (node (ref "USB1") (pin "2") (pinfunction "VBUS_2") (pintype "passive"))
    )
    (net (code "121") (name "/VIN") (class "Default")
      (node (ref "C33") (pin "2") (pinfunction "2_2") (pintype "passive"))
      (node (ref "C34") (pin "2") (pinfunction "2_2") (pintype "passive"))
      (node (ref "C39") (pin "2") (pinfunction "2_2") (pintype "passive"))
      (node (ref "C40") (pin "2") (pinfunction "2_2") (pintype "passive"))
      (node (ref "U13") (pin "2") (pinfunction "2_2") (pintype "passive"))
      (node (ref "U4") (pin "3") (pinfunction "Vin_3") (pintype "passive"))
      (node (ref "U5") (pin "3") (pinfunction "Vin_3") (pintype "passive"))
      (node (ref "U8") (pin "2") (pinfunction "2_2") (pintype "passive"))
    )
    (net (code "122") (name "DGND") (class "Default")
      (node (ref "C1") (pin "1") (pinfunction "1_1") (pintype "passive"))
      (node (ref "C10") (pin "1") (pinfunction "1_1") (pintype "passive"))
      (node (ref "C11") (pin "1") (pinfunction "1_1") (pintype "passive"))
      (node (ref "C12") (pin "1") (pinfunction "1_1") (pintype "passive"))
      (node (ref "C13") (pin "1") (pinfunction "1_1") (pintype "passive"))
      (node (ref "C14") (pin "1") (pinfunction "1_1") (pintype "passive"))
      (node (ref "C15") (pin "1") (pinfunction "1_1") (pintype "passive"))
      (node (ref "C16") (pin "2") (pinfunction "2_2") (pintype "passive"))
      (node (ref "C17") (pin "1") (pinfunction "1_1") (pintype "passive"))
      (node (ref "C18") (pin "1") (pinfunction "1_1") (pintype "passive"))
      (node (ref "C19") (pin "1") (pinfunction "1_1") (pintype "passive"))
      (node (ref "C2") (pin "1") (pinfunction "1_1") (pintype "passive"))
      (node (ref "C20") (pin "1") (pinfunction "1_1") (pintype "passive"))
      (node (ref "C21") (pin "1") (pinfunction "1_1") (pintype "passive"))
      (node (ref "C22") (pin "1") (pinfunction "1_1") (pintype "passive"))
      (node (ref "C23") (pin "1") (pinfunction "1_1") (pintype "passive"))
      (node (ref "C24") (pin "2") (pinfunction "2_2") (pintype "passive"))
      (node (ref "C25") (pin "1") (pinfunction "1_1") (pintype "passive"))
      (node (ref "C26") (pin "1") (pinfunction "1_1") (pintype "passive"))
      (node (ref "C27") (pin "1") (pinfunction "1_1") (pintype "passive"))
      (node (ref "C28") (pin "1") (pinfunction "1_1") (pintype "passive"))
      (node (ref "C29") (pin "1") (pinfunction "1_1") (pintype "passive"))
      (node (ref "C3") (pin "1") (pinfunction "1_1") (pintype "passive"))
      (node (ref "C30") (pin "1") (pinfunction "1_1") (pintype "passive"))
      (node (ref "C31") (pin "1") (pinfunction "1_1") (pintype "passive"))
      (node (ref "C32") (pin "2") (pinfunction "2_2") (pintype "passive"))
      (node (ref "C35") (pin "1") (pinfunction "1_1") (pintype "passive"))
      (node (ref "C36") (pin "1") (pinfunction "1_1") (pintype "passive"))
      (node (ref "C37") (pin "1") (pinfunction "1_1") (pintype "passive"))
      (node (ref "C38") (pin "1") (pinfunction "1_1") (pintype "passive"))
      (node (ref "C4") (pin "1") (pinfunction "1_1") (pintype "passive"))
      (node (ref "C41") (pin "1") (pinfunction "1_1") (pintype "passive"))
      (node (ref "C42") (pin "2") (pinfunction "2_2") (pintype "passive"))
      (node (ref "C43") (pin "1") (pinfunction "1_1") (pintype "passive"))
      (node (ref "C44") (pin "1") (pinfunction "1_1") (pintype "passive"))
      (node (ref "C45") (pin "1") (pinfunction "1_1") (pintype "passive"))
      (node (ref "C46") (pin "1") (pinfunction "1_1") (pintype "passive"))
      (node (ref "C47") (pin "1") (pinfunction "1_1") (pintype "passive"))
      (node (ref "C48") (pin "1") (pinfunction "1_1") (pintype "passive"))
      (node (ref "C49") (pin "1") (pinfunction "1_1") (pintype "passive"))
      (node (ref "C5") (pin "1") (pinfunction "1_1") (pintype "passive"))
      (node (ref "C50") (pin "1") (pinfunction "1_1") (pintype "passive"))
      (node (ref "C51") (pin "1") (pinfunction "1_1") (pintype "passive"))
      (node (ref "C6") (pin "1") (pinfunction "1_1") (pintype "passive"))
      (node (ref "C7") (pin "1") (pinfunction "1_1") (pintype "passive"))
      (node (ref "C8") (pin "2") (pinfunction "2_2") (pintype "passive"))
      (node (ref "C9") (pin "1") (pinfunction "1_1") (pintype "passive"))
      (node (ref "FPC2") (pin "1") (pinfunction "1_1") (pintype "passive"))
      (node (ref "FPC3") (pin "1") (pinfunction "1_1") (pintype "passive"))
      (node (ref "FPC4") (pin "1") (pinfunction "1_1") (pintype "passive"))
      (node (ref "H1") (pin "1") (pinfunction "1_1") (pintype "passive"))
      (node (ref "H10") (pin "1") (pinfunction "1_1") (pintype "passive"))
      (node (ref "H11") (pin "1") (pinfunction "1_1") (pintype "passive"))
      (node (ref "H12") (pin "1") (pinfunction "1_1") (pintype "passive"))
      (node (ref "H13") (pin "1") (pinfunction "1_1") (pintype "passive"))
      (node (ref "H14") (pin "1") (pinfunction "1_1") (pintype "passive"))
      (node (ref "H15") (pin "1") (pinfunction "1_1") (pintype "passive"))
      (node (ref "H2") (pin "1") (pinfunction "1_1") (pintype "passive"))
      (node (ref "H3") (pin "1") (pinfunction "1_1") (pintype "passive"))
      (node (ref "H4") (pin "1") (pinfunction "1_1") (pintype "passive"))
      (node (ref "H5") (pin "1") (pinfunction "1_1") (pintype "passive"))
      (node (ref "H6") (pin "1") (pinfunction "1_1") (pintype "passive"))
      (node (ref "H7") (pin "1") (pinfunction "1_1") (pintype "passive"))
      (node (ref "H8") (pin "1") (pinfunction "1_1") (pintype "passive"))
      (node (ref "H9") (pin "1") (pinfunction "1_1") (pintype "passive"))
      (node (ref "L2") (pin "15") (pinfunction "GND_15") (pintype "passive"))
      (node (ref "R15") (pin "2") (pinfunction "2_2") (pintype "passive"))
      (node (ref "R16") (pin "2") (pinfunction "2_2") (pintype "passive"))
      (node (ref "R2") (pin "1") (pinfunction "1_1") (pintype "passive"))
      (node (ref "R3") (pin "2") (pinfunction "2_2") (pintype "passive"))
      (node (ref "R4") (pin "2") (pinfunction "2_2") (pintype "passive"))
      (node (ref "U1") (pin "23") (pinfunction "VSS_1_23") (pintype "passive"))
      (node (ref "U1") (pin "35") (pinfunction "VSS_2_35") (pintype "passive"))
      (node (ref "U1") (pin "47") (pinfunction "VSS_3_47") (pintype "passive"))
      (node (ref "U1") (pin "8") (pinfunction "VSSA_8") (pintype "passive"))
      (node (ref "U15") (pin "1") (pinfunction "GND_1") (pintype "passive"))
      (node (ref "U16") (pin "23") (pinfunction "VSS_1_23") (pintype "passive"))
      (node (ref "U16") (pin "35") (pinfunction "VSS_2_35") (pintype "passive"))
      (node (ref "U16") (pin "47") (pinfunction "VSS_3_47") (pintype "passive"))
      (node (ref "U16") (pin "8") (pinfunction "VSSA_8") (pintype "passive"))
      (node (ref "U2") (pin "23") (pinfunction "VSS_1_23") (pintype "passive"))
      (node (ref "U2") (pin "35") (pinfunction "VSS_2_35") (pintype "passive"))
      (node (ref "U2") (pin "47") (pinfunction "VSS_3_47") (pintype "passive"))
      (node (ref "U2") (pin "8") (pinfunction "VSSA_8") (pintype "passive"))
      (node (ref "U3") (pin "23") (pinfunction "VSS_1_23") (pintype "passive"))
      (node (ref "U3") (pin "35") (pinfunction "VSS_2_35") (pintype "passive"))
      (node (ref "U3") (pin "47") (pinfunction "VSS_3_47") (pintype "passive"))
      (node (ref "U3") (pin "8") (pinfunction "VSSA_8") (pintype "passive"))
      (node (ref "U4") (pin "1") (pinfunction "GND/ADJ_1") (pintype "passive"))
      (node (ref "U5") (pin "1") (pinfunction "GND/ADJ_1") (pintype "passive"))
      (node (ref "U6") (pin "1") (pinfunction "-_1") (pintype "passive"))
      (node (ref "U7") (pin "1") (pinfunction "-_1") (pintype "passive"))
      (node (ref "U9") (pin "23") (pinfunction "VSS_1_23") (pintype "passive"))
      (node (ref "U9") (pin "35") (pinfunction "VSS_2_35") (pintype "passive"))
      (node (ref "U9") (pin "47") (pinfunction "VSS_3_47") (pintype "passive"))
      (node (ref "U9") (pin "8") (pinfunction "VSSA_8") (pintype "passive"))
      (node (ref "USB1") (pin "1") (pinfunction "GND_1") (pintype "passive"))
      (node (ref "USB1") (pin "12") (pinfunction "GND_12") (pintype "passive"))
      (node (ref "USB1") (pin "13") (pinfunction "SHELL_13") (pintype "passive"))
      (node (ref "USB1") (pin "14") (pinfunction "SHELL_14") (pintype "passive"))
    )
    (net (code "123") (name "Net-(Q1-Pad1)") (class "Default")
      (node (ref "Q1") (pin "1") (pinfunction "1_1") (pintype "passive"))
      (node (ref "R7") (pin "1") (pinfunction "1_1") (pintype "passive"))
    )
    (net (code "124") (name "Net-(Q2-Pad1)") (class "Default")
      (node (ref "Q2") (pin "1") (pinfunction "1_1") (pintype "passive"))
      (node (ref "R8") (pin "1") (pinfunction "1_1") (pintype "passive"))
    )
    (net (code "125") (name "Net-(U6-+)") (class "Default")
      (node (ref "R5") (pin "1") (pinfunction "1_1") (pintype "passive"))
      (node (ref "U6") (pin "2") (pinfunction "+_2") (pintype "passive"))
    )
    (net (code "126") (name "Net-(U7-+)") (class "Default")
      (node (ref "R6") (pin "2") (pinfunction "2_2") (pintype "passive"))
      (node (ref "U7") (pin "2") (pinfunction "+_2") (pintype "passive"))
    )
    (net (code "127") (name "Net-(USB1-CC1)") (class "Default")
      (node (ref "R15") (pin "1") (pinfunction "1_1") (pintype "passive"))
      (node (ref "USB1") (pin "4") (pinfunction "CC1_4") (pintype "passive"))
    )
    (net (code "128") (name "Net-(USB1-CC2)") (class "Default")
      (node (ref "R16") (pin "1") (pinfunction "1_1") (pintype "passive"))
      (node (ref "USB1") (pin "10") (pinfunction "CC2_10") (pintype "passive"))
    )
    (net (code "129") (name "PGND") (class "Default")
      (node (ref "C33") (pin "1") (pinfunction "1_1") (pintype "passive"))
      (node (ref "C34") (pin "1") (pinfunction "1_1") (pintype "passive"))
      (node (ref "C39") (pin "1") (pinfunction "1_1") (pintype "passive"))
      (node (ref "C40") (pin "1") (pinfunction "1_1") (pintype "passive"))
      (node (ref "R3") (pin "1") (pinfunction "1_1") (pintype "passive"))
      (node (ref "R4") (pin "1") (pinfunction "1_1") (pintype "passive"))
      (node (ref "U13") (pin "1") (pinfunction "1_1") (pintype "passive"))
      (node (ref "U8") (pin "1") (pinfunction "1_1") (pintype "passive"))
    )
    (net (code "130") (name "VCC_3.3") (class "Default")
      (node (ref "C1") (pin "2") (pinfunction "2_2") (pintype "passive"))
      (node (ref "C10") (pin "2") (pinfunction "2_2") (pintype "passive"))
      (node (ref "C11") (pin "2") (pinfunction "2_2") (pintype "passive"))
      (node (ref "C12") (pin "2") (pinfunction "2_2") (pintype "passive"))
      (node (ref "C13") (pin "2") (pinfunction "2_2") (pintype "passive"))
      (node (ref "C14") (pin "2") (pinfunction "2_2") (pintype "passive"))
      (node (ref "C17") (pin "2") (pinfunction "2_2") (pintype "passive"))
      (node (ref "C18") (pin "2") (pinfunction "2_2") (pintype "passive"))
      (node (ref "C19") (pin "2") (pinfunction "2_2") (pintype "passive"))
      (node (ref "C2") (pin "2") (pinfunction "2_2") (pintype "passive"))
      (node (ref "C20") (pin "2") (pinfunction "2_2") (pintype "passive"))
      (node (ref "C21") (pin "2") (pinfunction "2_2") (pintype "passive"))
      (node (ref "C22") (pin "2") (pinfunction "2_2") (pintype "passive"))
      (node (ref "C25") (pin "2") (pinfunction "2_2") (pintype "passive"))
      (node (ref "C26") (pin "2") (pinfunction "2_2") (pintype "passive"))
      (node (ref "C27") (pin "2") (pinfunction "2_2") (pintype "passive"))
      (node (ref "C28") (pin "2") (pinfunction "2_2") (pintype "passive"))
      (node (ref "C29") (pin "2") (pinfunction "2_2") (pintype "passive"))
      (node (ref "C3") (pin "2") (pinfunction "2_2") (pintype "passive"))
      (node (ref "C30") (pin "2") (pinfunction "2_2") (pintype "passive"))
      (node (ref "C35") (pin "2") (pinfunction "2_2") (pintype "passive"))
      (node (ref "C36") (pin "2") (pinfunction "2_2") (pintype "passive"))
      (node (ref "C4") (pin "2") (pinfunction "2_2") (pintype "passive"))
      (node (ref "C44") (pin "2") (pinfunction "2_2") (pintype "passive"))
      (node (ref "C45") (pin "2") (pinfunction "2_2") (pintype "passive"))
      (node (ref "C46") (pin "2") (pinfunction "2_2") (pintype "passive"))
      (node (ref "C47") (pin "2") (pinfunction "2_2") (pintype "passive"))
      (node (ref "C5") (pin "2") (pinfunction "2_2") (pintype "passive"))
      (node (ref "C50") (pin "2") (pinfunction "2_2") (pintype "passive"))
      (node (ref "C51") (pin "2") (pinfunction "2_2") (pintype "passive"))
      (node (ref "C6") (pin "2") (pinfunction "2_2") (pintype "passive"))
      (node (ref "C9") (pin "2") (pinfunction "2_2") (pintype "passive"))
      (node (ref "H1") (pin "4") (pinfunction "4_4") (pintype "passive"))
      (node (ref "H10") (pin "4") (pinfunction "4_4") (pintype "passive"))
      (node (ref "H11") (pin "4") (pinfunction "4_4") (pintype "passive"))
      (node (ref "H14") (pin "4") (pinfunction "4_4") (pintype "passive"))
      (node (ref "H15") (pin "4") (pinfunction "4_4") (pintype "passive"))
      (node (ref "H2") (pin "4") (pinfunction "4_4") (pintype "passive"))
      (node (ref "H4") (pin "4") (pinfunction "4_4") (pintype "passive"))
      (node (ref "H5") (pin "4") (pinfunction "4_4") (pintype "passive"))
      (node (ref "H7") (pin "4") (pinfunction "4_4") (pintype "passive"))
      (node (ref "H8") (pin "4") (pinfunction "4_4") (pintype "passive"))
      (node (ref "R1") (pin "1") (pinfunction "1_1") (pintype "passive"))
      (node (ref "R5") (pin "2") (pinfunction "2_2") (pintype "passive"))
      (node (ref "U1") (pin "1") (pinfunction "VBAT_1") (pintype "passive"))
      (node (ref "U1") (pin "24") (pinfunction "VDD_1_24") (pintype "passive"))
      (node (ref "U1") (pin "36") (pinfunction "VDD_2_36") (pintype "passive"))
      (node (ref "U1") (pin "48") (pinfunction "VDD_3_48") (pintype "passive"))
      (node (ref "U1") (pin "9") (pinfunction "VDDA_9") (pintype "passive"))
      (node (ref "U16") (pin "1") (pinfunction "VBAT_1") (pintype "passive"))
      (node (ref "U16") (pin "24") (pinfunction "VDD_1_24") (pintype "passive"))
      (node (ref "U16") (pin "36") (pinfunction "VDD_2_36") (pintype "passive"))
      (node (ref "U16") (pin "48") (pinfunction "VDD_3_48") (pintype "passive"))
      (node (ref "U16") (pin "9") (pinfunction "VDDA_9") (pintype "passive"))
      (node (ref "U2") (pin "1") (pinfunction "VBAT_1") (pintype "passive"))
      (node (ref "U2") (pin "24") (pinfunction "VDD_1_24") (pintype "passive"))
      (node (ref "U2") (pin "36") (pinfunction "VDD_2_36") (pintype "passive"))
      (node (ref "U2") (pin "48") (pinfunction "VDD_3_48") (pintype "passive"))
      (node (ref "U2") (pin "9") (pinfunction "VDDA_9") (pintype "passive"))
      (node (ref "U3") (pin "1") (pinfunction "VBAT_1") (pintype "passive"))
      (node (ref "U3") (pin "24") (pinfunction "VDD_1_24") (pintype "passive"))
      (node (ref "U3") (pin "36") (pinfunction "VDD_2_36") (pintype "passive"))
      (node (ref "U3") (pin "48") (pinfunction "VDD_3_48") (pintype "passive"))
      (node (ref "U3") (pin "9") (pinfunction "VDDA_9") (pintype "passive"))
      (node (ref "U4") (pin "4") (pinfunction "Vout_4") (pintype "passive"))
      (node (ref "U9") (pin "1") (pinfunction "VBAT_1") (pintype "passive"))
      (node (ref "U9") (pin "24") (pinfunction "VDD_1_24") (pintype "passive"))
      (node (ref "U9") (pin "36") (pinfunction "VDD_2_36") (pintype "passive"))
      (node (ref "U9") (pin "48") (pinfunction "VDD_3_48") (pintype "passive"))
      (node (ref "U9") (pin "9") (pinfunction "VDDA_9") (pintype "passive"))
    )
    (net (code "131") (name "VCC_3.3_ESP32_SENSOR") (class "Default")
      (node (ref "C37") (pin "2") (pinfunction "2_2") (pintype "passive"))
      (node (ref "C38") (pin "2") (pinfunction "2_2") (pintype "passive"))
      (node (ref "C48") (pin "2") (pinfunction "2_2") (pintype "passive"))
      (node (ref "C49") (pin "2") (pinfunction "2_2") (pintype "passive"))
      (node (ref "FPC2") (pin "6") (pinfunction "6_6") (pintype "passive"))
      (node (ref "FPC3") (pin "6") (pinfunction "6_6") (pintype "passive"))
      (node (ref "FPC4") (pin "6") (pinfunction "6_6") (pintype "passive"))
      (node (ref "H12") (pin "6") (pinfunction "6_6") (pintype "passive"))
      (node (ref "H13") (pin "6") (pinfunction "6_6") (pintype "passive"))
      (node (ref "H3") (pin "6") (pinfunction "6_6") (pintype "passive"))
      (node (ref "H6") (pin "6") (pinfunction "6_6") (pintype "passive"))
      (node (ref "H9") (pin "6") (pinfunction "6_6") (pintype "passive"))
      (node (ref "L2") (pin "8") (pinfunction "VCC_8") (pintype "passive"))
      (node (ref "R11") (pin "2") (pinfunction "2_2") (pintype "passive"))
      (node (ref "R6") (pin "1") (pinfunction "1_1") (pintype "passive"))
      (node (ref "U15") (pin "4") (pinfunction "V3_4") (pintype "passive"))
      (node (ref "U5") (pin "4") (pinfunction "Vout_4") (pintype "passive"))
    )
    (net (code "132") (name "unconnected-(FPC1-Pad1)") (class "Default")
      (node (ref "FPC1") (pin "1") (pinfunction "1_1") (pintype "passive"))
    )
    (net (code "133") (name "unconnected-(FPC1-Pad41)") (class "Default")
      (node (ref "FPC1") (pin "41") (pinfunction "41_41") (pintype "passive"))
    )
    (net (code "134") (name "unconnected-(FPC1-Pad42)") (class "Default")
      (node (ref "FPC1") (pin "42") (pinfunction "42_42") (pintype "passive"))
    )
    (net (code "135") (name "unconnected-(FPC2-Pad7)") (class "Default")
      (node (ref "FPC2") (pin "7") (pinfunction "7_7") (pintype "passive"))
    )
    (net (code "136") (name "unconnected-(FPC2-Pad8)") (class "Default")
      (node (ref "FPC2") (pin "8") (pinfunction "8_8") (pintype "passive"))
    )
    (net (code "137") (name "unconnected-(FPC3-Pad7)") (class "Default")
      (node (ref "FPC3") (pin "7") (pinfunction "7_7") (pintype "passive"))
    )
    (net (code "138") (name "unconnected-(FPC3-Pad8)") (class "Default")
      (node (ref "FPC3") (pin "8") (pinfunction "8_8") (pintype "passive"))
    )
    (net (code "139") (name "unconnected-(FPC4-Pad7)") (class "Default")
      (node (ref "FPC4") (pin "7") (pinfunction "7_7") (pintype "passive"))
    )
    (net (code "140") (name "unconnected-(FPC4-Pad8)") (class "Default")
      (node (ref "FPC4") (pin "8") (pinfunction "8_8") (pintype "passive"))
    )
    (net (code "141") (name "unconnected-(L2-NC-Pad9)") (class "Default")
      (node (ref "L2") (pin "9") (pinfunction "NC_9") (pintype "passive"))
    )
    (net (code "142") (name "unconnected-(L2-NC-Pad10)") (class "Default")
      (node (ref "L2") (pin "10") (pinfunction "NC_10") (pintype "passive"))
    )
    (net (code "143") (name "unconnected-(L2-NC-Pad11)") (class "Default")
      (node (ref "L2") (pin "11") (pinfunction "NC_11") (pintype "passive"))
    )
    (net (code "144") (name "unconnected-(L2-NC-Pad14)") (class "Default")
      (node (ref "L2") (pin "14") (pinfunction "NC_14") (pintype "passive"))
    )
    (net (code "145") (name "unconnected-(U1-PA3-Pad13)") (class "Default")
      (node (ref "U1") (pin "13") (pinfunction "PA3_13") (pintype "passive"))
    )
    (net (code "146") (name "unconnected-(U1-PA4-Pad14)") (class "Default")
      (node (ref "U1") (pin "14") (pinfunction "PA4_14") (pintype "passive"))
    )
    (net (code "147") (name "unconnected-(U1-PA5-Pad15)") (class "Default")
      (node (ref "U1") (pin "15") (pinfunction "PA5_15") (pintype "passive"))
    )
    (net (code "148") (name "unconnected-(U1-PA8-Pad29)") (class "Default")
      (node (ref "U1") (pin "29") (pinfunction "PA8_29") (pintype "passive"))
    )
    (net (code "149") (name "unconnected-(U1-PA11-Pad32)") (class "Default")
      (node (ref "U1") (pin "32") (pinfunction "PA11_32") (pintype "passive"))
    )
    (net (code "150") (name "unconnected-(U1-PA12-Pad33)") (class "Default")
      (node (ref "U1") (pin "33") (pinfunction "PA12_33") (pintype "passive"))
    )
    (net (code "151") (name "unconnected-(U1-PB1-Pad19)") (class "Default")
      (node (ref "U1") (pin "19") (pinfunction "PB1_19") (pintype "passive"))
    )
    (net (code "152") (name "unconnected-(U1-PB2-Pad20)") (class "Default")
      (node (ref "U1") (pin "20") (pinfunction "PB2_20") (pintype "passive"))
    )
    (net (code "153") (name "unconnected-(U1-PB9-Pad46)") (class "Default")
      (node (ref "U1") (pin "46") (pinfunction "PB9_46") (pintype "passive"))
    )
    (net (code "154") (name "unconnected-(U1-PB10-Pad21)") (class "Default")
      (node (ref "U1") (pin "21") (pinfunction "PB10_21") (pintype "passive"))
    )
    (net (code "155") (name "unconnected-(U1-PB11-Pad22)") (class "Default")
      (node (ref "U1") (pin "22") (pinfunction "PB11_22") (pintype "passive"))
    )
    (net (code "156") (name "unconnected-(U1-PC13-TAMPER-RTC-Pad2)") (class "Default")
      (node (ref "U1") (pin "2") (pinfunction "PC13-TAMPER-RTC_2") (pintype "passive"))
    )
    (net (code "157") (name "unconnected-(U1-PC14-OSC32_IN-Pad3)") (class "Default")
      (node (ref "U1") (pin "3") (pinfunction "PC14-OSC32_IN_3") (pintype "passive"))
    )
    (net (code "158") (name "unconnected-(U1-PC15-OSC32_OUT-Pad4)") (class "Default")
      (node (ref "U1") (pin "4") (pinfunction "PC15-OSC32_OUT_4") (pintype "passive"))
    )
    (net (code "159") (name "unconnected-(U2-PA3-Pad13)") (class "Default")
      (node (ref "U2") (pin "13") (pinfunction "PA3_13") (pintype "passive"))
    )
    (net (code "160") (name "unconnected-(U2-PA4-Pad14)") (class "Default")
      (node (ref "U2") (pin "14") (pinfunction "PA4_14") (pintype "passive"))
    )
    (net (code "161") (name "unconnected-(U2-PA5-Pad15)") (class "Default")
      (node (ref "U2") (pin "15") (pinfunction "PA5_15") (pintype "passive"))
    )
    (net (code "162") (name "unconnected-(U2-PA8-Pad29)") (class "Default")
      (node (ref "U2") (pin "29") (pinfunction "PA8_29") (pintype "passive"))
    )
    (net (code "163") (name "unconnected-(U2-PA11-Pad32)") (class "Default")
      (node (ref "U2") (pin "32") (pinfunction "PA11_32") (pintype "passive"))
    )
    (net (code "164") (name "unconnected-(U2-PA12-Pad33)") (class "Default")
      (node (ref "U2") (pin "33") (pinfunction "PA12_33") (pintype "passive"))
    )
    (net (code "165") (name "unconnected-(U2-PB1-Pad19)") (class "Default")
      (node (ref "U2") (pin "19") (pinfunction "PB1_19") (pintype "passive"))
    )
    (net (code "166") (name "unconnected-(U2-PB2-Pad20)") (class "Default")
      (node (ref "U2") (pin "20") (pinfunction "PB2_20") (pintype "passive"))
    )
    (net (code "167") (name "unconnected-(U2-PB9-Pad46)") (class "Default")
      (node (ref "U2") (pin "46") (pinfunction "PB9_46") (pintype "passive"))
    )
    (net (code "168") (name "unconnected-(U2-PB10-Pad21)") (class "Default")
      (node (ref "U2") (pin "21") (pinfunction "PB10_21") (pintype "passive"))
    )
    (net (code "169") (name "unconnected-(U2-PB11-Pad22)") (class "Default")
      (node (ref "U2") (pin "22") (pinfunction "PB11_22") (pintype "passive"))
    )
    (net (code "170") (name "unconnected-(U2-PC13-TAMPER-RTC-Pad2)") (class "Default")
      (node (ref "U2") (pin "2") (pinfunction "PC13-TAMPER-RTC_2") (pintype "passive"))
    )
    (net (code "171") (name "unconnected-(U2-PC14-OSC32_IN-Pad3)") (class "Default")
      (node (ref "U2") (pin "3") (pinfunction "PC14-OSC32_IN_3") (pintype "passive"))
    )
    (net (code "172") (name "unconnected-(U2-PC15-OSC32_OUT-Pad4)") (class "Default")
      (node (ref "U2") (pin "4") (pinfunction "PC15-OSC32_OUT_4") (pintype "passive"))
    )
    (net (code "173") (name "unconnected-(U3-PA3-Pad13)") (class "Default")
      (node (ref "U3") (pin "13") (pinfunction "PA3_13") (pintype "passive"))
    )
    (net (code "174") (name "unconnected-(U3-PA4-Pad14)") (class "Default")
      (node (ref "U3") (pin "14") (pinfunction "PA4_14") (pintype "passive"))
    )
    (net (code "175") (name "unconnected-(U3-PA5-Pad15)") (class "Default")
      (node (ref "U3") (pin "15") (pinfunction "PA5_15") (pintype "passive"))
    )
    (net (code "176") (name "unconnected-(U3-PA8-Pad29)") (class "Default")
      (node (ref "U3") (pin "29") (pinfunction "PA8_29") (pintype "passive"))
    )
    (net (code "177") (name "unconnected-(U3-PA11-Pad32)") (class "Default")
      (node (ref "U3") (pin "32") (pinfunction "PA11_32") (pintype "passive"))
    )
    (net (code "178") (name "unconnected-(U3-PA12-Pad33)") (class "Default")
      (node (ref "U3") (pin "33") (pinfunction "PA12_33") (pintype "passive"))
    )
    (net (code "179") (name "unconnected-(U3-PB1-Pad19)") (class "Default")
      (node (ref "U3") (pin "19") (pinfunction "PB1_19") (pintype "passive"))
    )
    (net (code "180") (name "unconnected-(U3-PB2-Pad20)") (class "Default")
      (node (ref "U3") (pin "20") (pinfunction "PB2_20") (pintype "passive"))
    )
    (net (code "181") (name "unconnected-(U3-PB9-Pad46)") (class "Default")
      (node (ref "U3") (pin "46") (pinfunction "PB9_46") (pintype "passive"))
    )
    (net (code "182") (name "unconnected-(U3-PB10-Pad21)") (class "Default")
      (node (ref "U3") (pin "21") (pinfunction "PB10_21") (pintype "passive"))
    )
    (net (code "183") (name "unconnected-(U3-PB11-Pad22)") (class "Default")
      (node (ref "U3") (pin "22") (pinfunction "PB11_22") (pintype "passive"))
    )
    (net (code "184") (name "unconnected-(U3-PC13-TAMPER-RTC-Pad2)") (class "Default")
      (node (ref "U3") (pin "2") (pinfunction "PC13-TAMPER-RTC_2") (pintype "passive"))
    )
    (net (code "185") (name "unconnected-(U3-PC14-OSC32_IN-Pad3)") (class "Default")
      (node (ref "U3") (pin "3") (pinfunction "PC14-OSC32_IN_3") (pintype "passive"))
    )
    (net (code "186") (name "unconnected-(U3-PC15-OSC32_OUT-Pad4)") (class "Default")
      (node (ref "U3") (pin "4") (pinfunction "PC15-OSC32_OUT_4") (pintype "passive"))
    )
    (net (code "187") (name "unconnected-(U4-Vout-Pad2)") (class "Default")
      (node (ref "U4") (pin "2") (pinfunction "Vout_2") (pintype "passive"))
    )
    (net (code "188") (name "unconnected-(U5-Vout-Pad2)") (class "Default")
      (node (ref "U5") (pin "2") (pinfunction "Vout_2") (pintype "passive"))
    )
    (net (code "189") (name "unconnected-(U8-Pad3)") (class "Default")
      (node (ref "U8") (pin "3") (pinfunction "3_3") (pintype "passive"))
    )
    (net (code "190") (name "unconnected-(U8-Pad4)") (class "Default")
      (node (ref "U8") (pin "4") (pinfunction "4_4") (pintype "passive"))
    )
    (net (code "191") (name "unconnected-(U9-PA3-Pad13)") (class "Default")
      (node (ref "U9") (pin "13") (pinfunction "PA3_13") (pintype "passive"))
    )
    (net (code "192") (name "unconnected-(U9-PA8-Pad29)") (class "Default")
      (node (ref "U9") (pin "29") (pinfunction "PA8_29") (pintype "passive"))
    )
    (net (code "193") (name "unconnected-(U9-PA11-Pad32)") (class "Default")
      (node (ref "U9") (pin "32") (pinfunction "PA11_32") (pintype "passive"))
    )
    (net (code "194") (name "unconnected-(U9-PA12-Pad33)") (class "Default")
      (node (ref "U9") (pin "33") (pinfunction "PA12_33") (pintype "passive"))
    )
    (net (code "195") (name "unconnected-(U9-PB6-Pad42)") (class "Default")
      (node (ref "U9") (pin "42") (pinfunction "PB6_42") (pintype "passive"))
    )
    (net (code "196") (name "unconnected-(U9-PB7-Pad43)") (class "Default")
      (node (ref "U9") (pin "43") (pinfunction "PB7_43") (pintype "passive"))
    )
    (net (code "197") (name "unconnected-(U9-PB8-Pad45)") (class "Default")
      (node (ref "U9") (pin "45") (pinfunction "PB8_45") (pintype "passive"))
    )
    (net (code "198") (name "unconnected-(U9-PB9-Pad46)") (class "Default")
      (node (ref "U9") (pin "46") (pinfunction "PB9_46") (pintype "passive"))
    )
    (net (code "199") (name "unconnected-(U9-PB11-Pad22)") (class "Default")
      (node (ref "U9") (pin "22") (pinfunction "PB11_22") (pintype "passive"))
    )
    (net (code "200") (name "unconnected-(U9-PC13-TAMPER-RTC-Pad2)") (class "Default")
      (node (ref "U9") (pin "2") (pinfunction "PC13-TAMPER-RTC_2") (pintype "passive"))
    )
    (net (code "201") (name "unconnected-(U9-PC14-OSC32_IN-Pad3)") (class "Default")
      (node (ref "U9") (pin "3") (pinfunction "PC14-OSC32_IN_3") (pintype "passive"))
    )
    (net (code "202") (name "unconnected-(U9-PC15-OSC32_OUT-Pad4)") (class "Default")
      (node (ref "U9") (pin "4") (pinfunction "PC15-OSC32_OUT_4") (pintype "passive"))
    )
    (net (code "203") (name "unconnected-(U13-Pad3)") (class "Default")
      (node (ref "U13") (pin "3") (pinfunction "3_3") (pintype "passive"))
    )
    (net (code "204") (name "unconnected-(U13-Pad4)") (class "Default")
      (node (ref "U13") (pin "4") (pinfunction "4_4") (pintype "passive"))
    )
    (net (code "205") (name "unconnected-(U15-CTS#-Pad9)") (class "Default")
      (node (ref "U15") (pin "9") (pinfunction "CTS#_9") (pintype "passive+no_connect"))
    )
    (net (code "206") (name "unconnected-(U15-DCD#-Pad12)") (class "Default")
      (node (ref "U15") (pin "12") (pinfunction "DCD#_12") (pintype "passive+no_connect"))
    )
    (net (code "207") (name "unconnected-(U15-DSR#-Pad10)") (class "Default")
      (node (ref "U15") (pin "10") (pinfunction "DSR#_10") (pintype "passive+no_connect"))
    )
    (net (code "208") (name "unconnected-(U15-NC.-Pad7)") (class "Default")
      (node (ref "U15") (pin "7") (pinfunction "NC._7") (pintype "passive+no_connect"))
    )
    (net (code "209") (name "unconnected-(U15-NC.-Pad8)") (class "Default")
      (node (ref "U15") (pin "8") (pinfunction "NC._8") (pintype "passive+no_connect"))
    )
    (net (code "210") (name "unconnected-(U15-R232-Pad15)") (class "Default")
      (node (ref "U15") (pin "15") (pinfunction "R232_15") (pintype "passive+no_connect"))
    )
    (net (code "211") (name "unconnected-(U15-RI#-Pad11)") (class "Default")
      (node (ref "U15") (pin "11") (pinfunction "RI#_11") (pintype "passive+no_connect"))
    )
    (net (code "212") (name "unconnected-(U16-PA3-Pad13)") (class "Default")
      (node (ref "U16") (pin "13") (pinfunction "PA3_13") (pintype "passive"))
    )
    (net (code "213") (name "unconnected-(U16-PA4-Pad14)") (class "Default")
      (node (ref "U16") (pin "14") (pinfunction "PA4_14") (pintype "passive"))
    )
    (net (code "214") (name "unconnected-(U16-PA5-Pad15)") (class "Default")
      (node (ref "U16") (pin "15") (pinfunction "PA5_15") (pintype "passive"))
    )
    (net (code "215") (name "unconnected-(U16-PA8-Pad29)") (class "Default")
      (node (ref "U16") (pin "29") (pinfunction "PA8_29") (pintype "passive"))
    )
    (net (code "216") (name "unconnected-(U16-PA11-Pad32)") (class "Default")
      (node (ref "U16") (pin "32") (pinfunction "PA11_32") (pintype "passive"))
    )
    (net (code "217") (name "unconnected-(U16-PA12-Pad33)") (class "Default")
      (node (ref "U16") (pin "33") (pinfunction "PA12_33") (pintype "passive"))
    )
    (net (code "218") (name "unconnected-(U16-PB1-Pad19)") (class "Default")
      (node (ref "U16") (pin "19") (pinfunction "PB1_19") (pintype "passive"))
    )
    (net (code "219") (name "unconnected-(U16-PB2-Pad20)") (class "Default")
      (node (ref "U16") (pin "20") (pinfunction "PB2_20") (pintype "passive"))
    )
    (net (code "220") (name "unconnected-(U16-PB9-Pad46)") (class "Default")
      (node (ref "U16") (pin "46") (pinfunction "PB9_46") (pintype "passive"))
    )
    (net (code "221") (name "unconnected-(U16-PB10-Pad21)") (class "Default")
      (node (ref "U16") (pin "21") (pinfunction "PB10_21") (pintype "passive"))
    )
    (net (code "222") (name "unconnected-(U16-PB11-Pad22)") (class "Default")
      (node (ref "U16") (pin "22") (pinfunction "PB11_22") (pintype "passive"))
    )
    (net (code "223") (name "unconnected-(U16-PC13-TAMPER-RTC-Pad2)") (class "Default")
      (node (ref "U16") (pin "2") (pinfunction "PC13-TAMPER-RTC_2") (pintype "passive"))
    )
    (net (code "224") (name "unconnected-(U16-PC14-OSC32_IN-Pad3)") (class "Default")
      (node (ref "U16") (pin "3") (pinfunction "PC14-OSC32_IN_3") (pintype "passive"))
    )
    (net (code "225") (name "unconnected-(U16-PC15-OSC32_OUT-Pad4)") (class "Default")
      (node (ref "U16") (pin "4") (pinfunction "PC15-OSC32_OUT_4") (pintype "passive"))
    )
    (net (code "226") (name "unconnected-(USB1-SBU1-Pad9)") (class "Default")
      (node (ref "USB1") (pin "9") (pinfunction "SBU1_9") (pintype "passive+no_connect"))
    )
    (net (code "227") (name "unconnected-(USB1-SBU2-Pad3)") (class "Default")
      (node (ref "USB1") (pin "3") (pinfunction "SBU2_3") (pintype "passive+no_connect"))
    )
  )
)
